# master_wiring.net
KiCad netlist of a schematic drawn in EAGLE
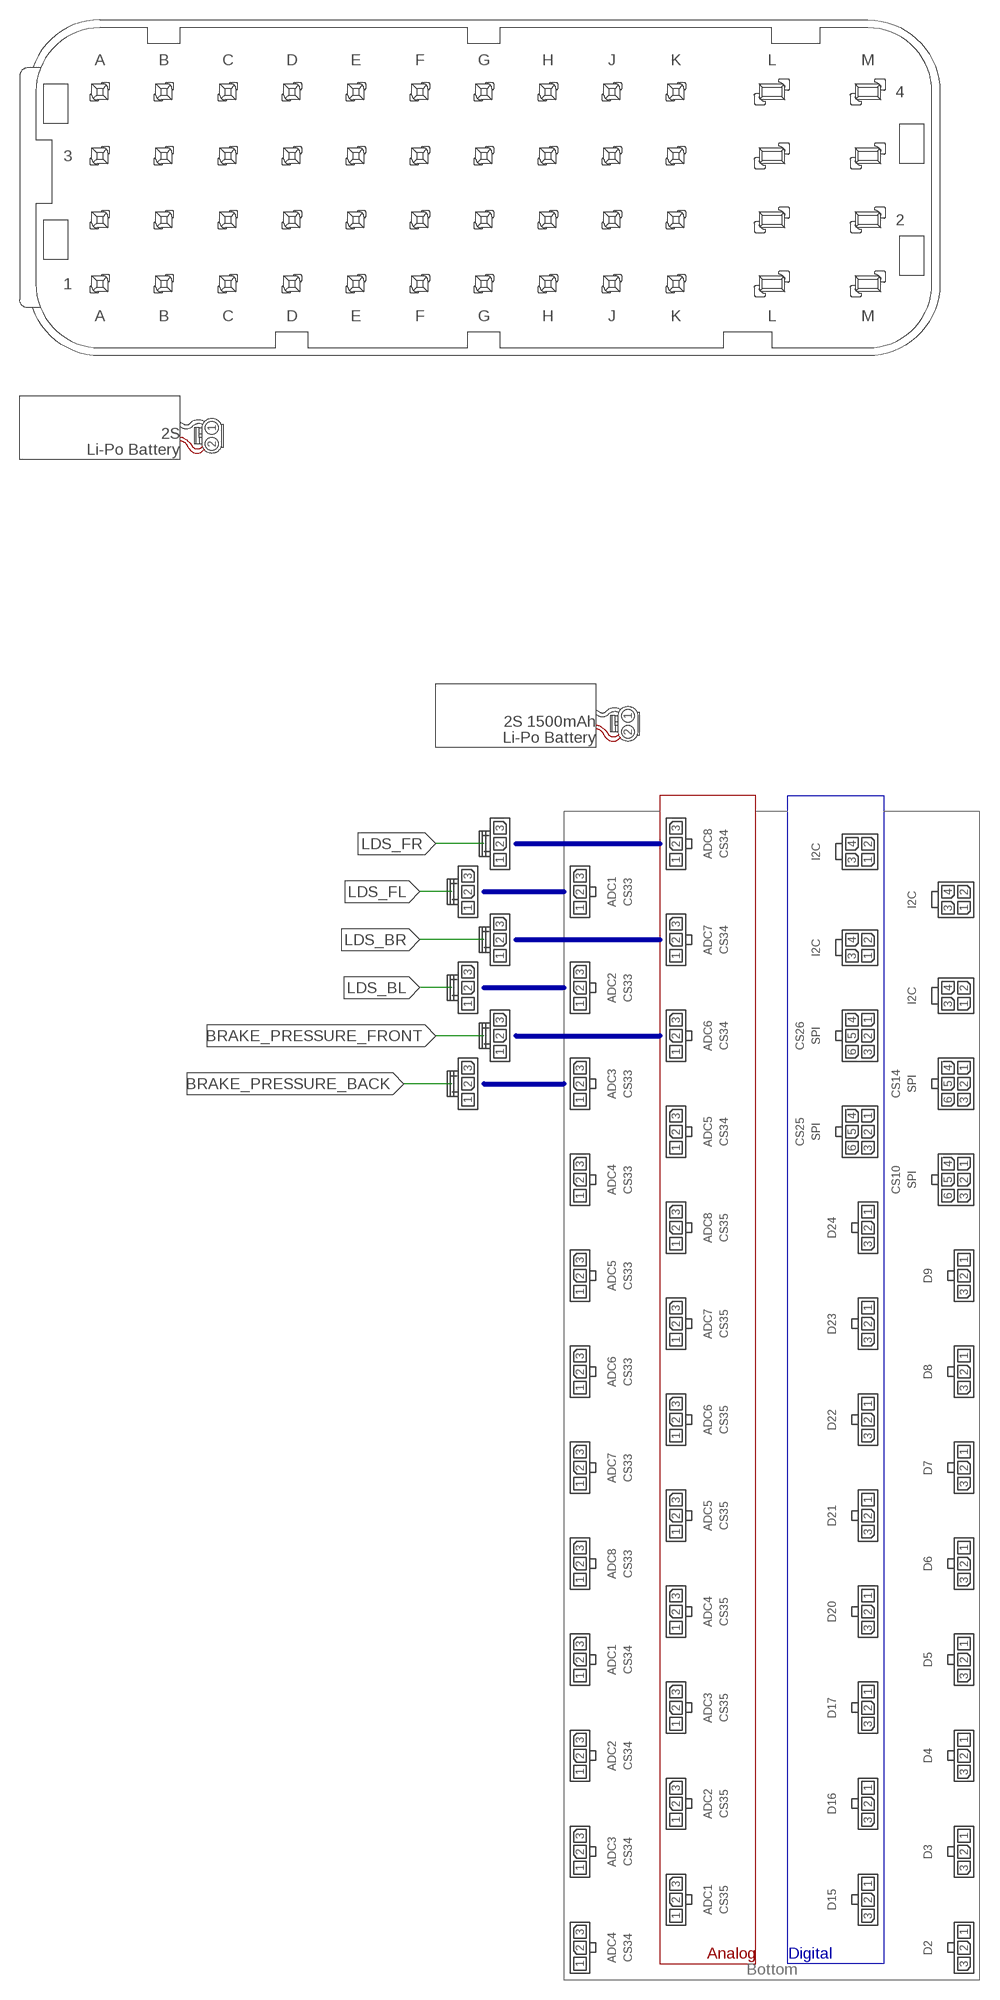
[diagram p0: schematic, sheet 1, part 1 of 2]
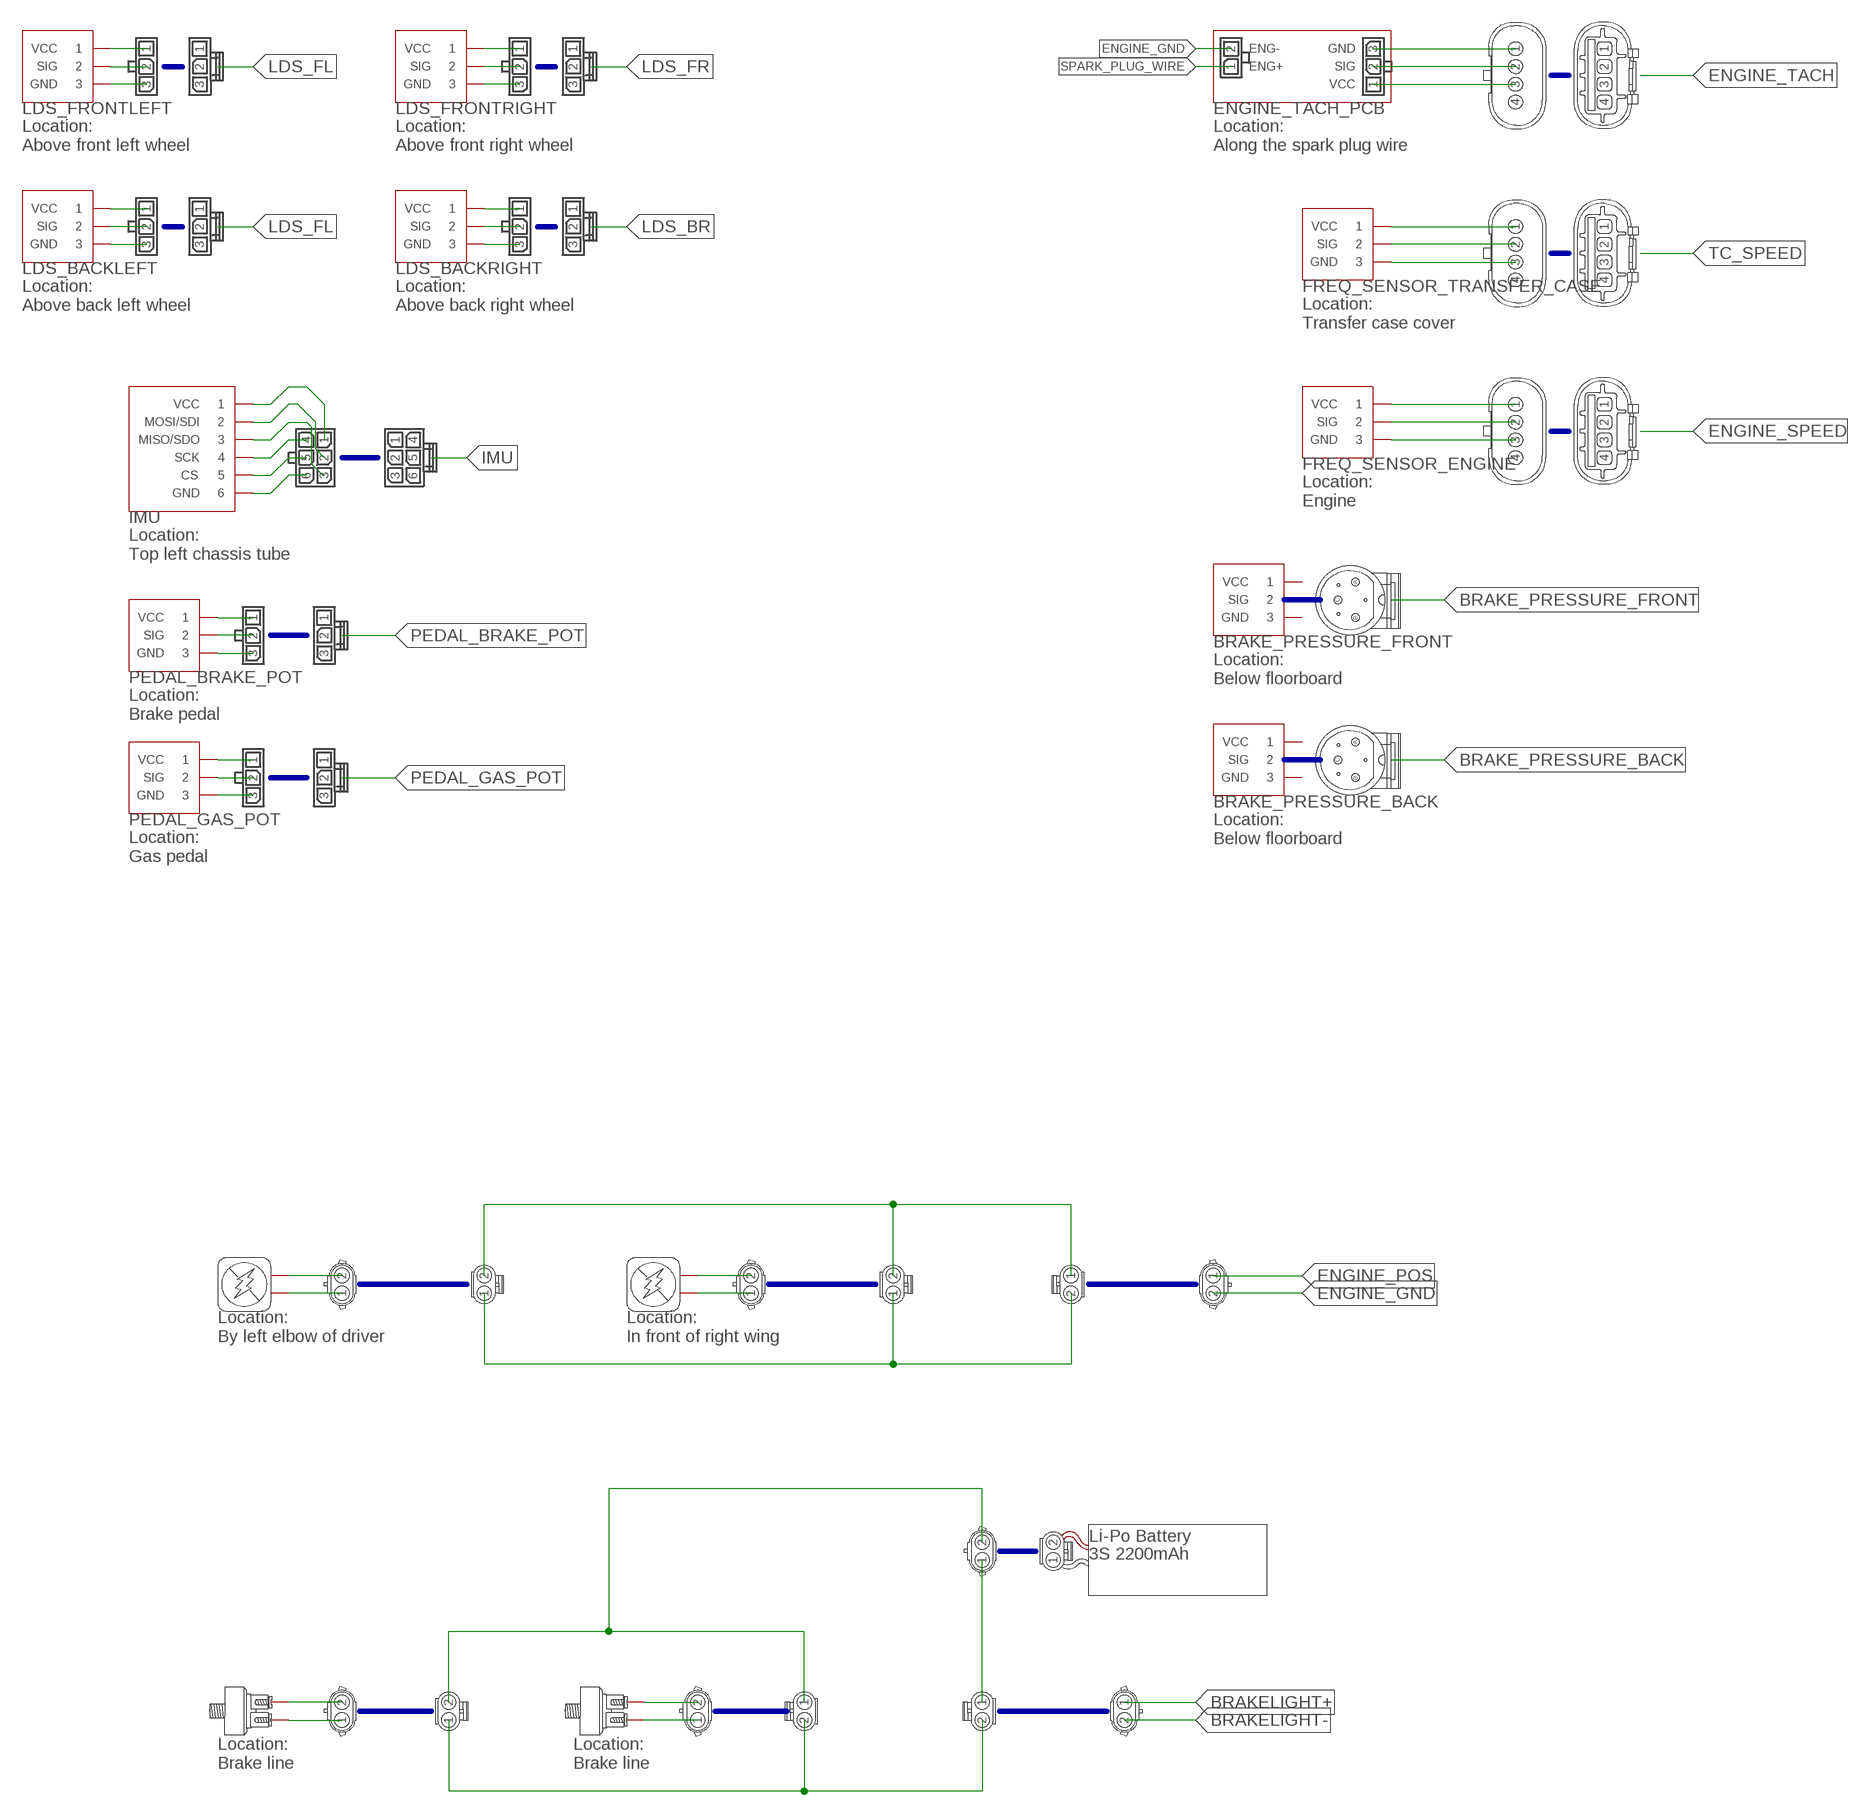
[diagram p1: schematic, sheet 1, part 2 of 2]

(export (version "E")
  (design (tool "Eeschema 10.0.6"))
  (components
    (comp (ref "BRAKE_PRESSURE_BACK")
      (value "SENSOR_1X3")
      (footprint "eagle-import:PINS_3")
      (libsource (lib "eagle-import") (part "SENSOR_1X3"))
    )
    (comp (ref "BRAKE_PRESSURE_FRONT")
      (value "SENSOR_1X3")
      (footprint "eagle-import:PINS_3")
      (libsource (lib "eagle-import") (part "SENSOR_1X3"))
    )
    (comp (ref "ENGINE_TACH_PCB")
      (value "ENGINE_TACH_PCB")
      (footprint "eagle-import:PINS_7")
      (libsource (lib "eagle-import") (part "ENGINE_TACH_PCB"))
    )
    (comp (ref "FREQ_SENSOR_ENGINE")
      (value "SENSOR_1X3")
      (footprint "eagle-import:PINS_3")
      (libsource (lib "eagle-import") (part "SENSOR_1X3"))
    )
    (comp (ref "FREQ_SENSOR_TRANSFER_CASE")
      (value "SENSOR_1X3")
      (footprint "eagle-import:PINS_3")
      (libsource (lib "eagle-import") (part "SENSOR_1X3"))
    )
    (comp (ref "IMU")
      (value "SENSOR_SPI_2X3")
      (footprint "eagle-import:PINS_7")
      (libsource (lib "eagle-import") (part "SENSOR_SPI_2X3"))
    )
    (comp (ref "LDS_BACKLEFT")
      (value "SENSOR_1X3")
      (footprint "eagle-import:PINS_3")
      (libsource (lib "eagle-import") (part "SENSOR_1X3"))
    )
    (comp (ref "LDS_BACKRIGHT")
      (value "SENSOR_1X3")
      (footprint "eagle-import:PINS_3")
      (libsource (lib "eagle-import") (part "SENSOR_1X3"))
    )
    (comp (ref "LDS_FRONTLEFT")
      (value "SENSOR_1X3")
      (footprint "eagle-import:PINS_3")
      (libsource (lib "eagle-import") (part "SENSOR_1X3"))
    )
    (comp (ref "LDS_FRONTRIGHT")
      (value "SENSOR_1X3")
      (footprint "eagle-import:PINS_3")
      (libsource (lib "eagle-import") (part "SENSOR_1X3"))
    )
    (comp (ref "PEDAL_BRAKE_POT")
      (value "SENSOR_1X3")
      (footprint "eagle-import:PINS_3")
      (libsource (lib "eagle-import") (part "SENSOR_1X3"))
    )
    (comp (ref "PEDAL_GAS_POT")
      (value "SENSOR_1X3")
      (footprint "eagle-import:PINS_3")
      (libsource (lib "eagle-import") (part "SENSOR_1X3"))
    )
    (comp (ref "U$1")
      (value "MICROFIT_1X3_MALE")
      (footprint "eagle-import:PINS_4")
      (libsource (lib "eagle-import") (part "MICROFIT_1X3_MALE"))
    )
    (comp (ref "U$2")
      (value "CMC_48PIN_PLUG_PCB")
      (footprint "eagle-import:PINS_49")
      (libsource (lib "eagle-import") (part "CMC_48PIN_PLUG_PCB"))
    )
    (comp (ref "U$3")
      (value "AUXDAQ_REV2")
      (footprint "eagle-import:PINS_200")
      (libsource (lib "eagle-import") (part "AUXDAQ_REV2"))
    )
    (comp (ref "U$4")
      (value "SKIDOO_KILLSWITCH")
      (footprint "eagle-import:PINS_3")
      (libsource (lib "eagle-import") (part "SKIDOO_KILLSWITCH"))
    )
    (comp (ref "U$5")
      (value "WEATHERPACK_1X2_MALE")
      (footprint "eagle-import:PINS_3")
      (libsource (lib "eagle-import") (part "WEATHERPACK_1X2_MALE"))
    )
    (comp (ref "U$6")
      (value "WEATHERPACK_1X2_FEMALE")
      (footprint "eagle-import:PINS_3")
      (libsource (lib "eagle-import") (part "WEATHERPACK_1X2_FEMALE"))
    )
    (comp (ref "U$7")
      (value "WEATHERPACK_1X2_MALE")
      (footprint "eagle-import:PINS_3")
      (libsource (lib "eagle-import") (part "WEATHERPACK_1X2_MALE"))
    )
    (comp (ref "U$8")
      (value "WEATHERPACK_1X2_MALE")
      (footprint "eagle-import:PINS_3")
      (libsource (lib "eagle-import") (part "WEATHERPACK_1X2_MALE"))
    )
    (comp (ref "U$9")
      (value "SKIDOO_KILLSWITCH")
      (footprint "eagle-import:PINS_3")
      (libsource (lib "eagle-import") (part "SKIDOO_KILLSWITCH"))
    )
    (comp (ref "U$10")
      (value "WEATHERPACK_1X2_FEMALE")
      (footprint "eagle-import:PINS_3")
      (libsource (lib "eagle-import") (part "WEATHERPACK_1X2_FEMALE"))
    )
    (comp (ref "U$11")
      (value "WEATHERPACK_1X2_FEMALE")
      (footprint "eagle-import:PINS_3")
      (libsource (lib "eagle-import") (part "WEATHERPACK_1X2_FEMALE"))
    )
    (comp (ref "U$12")
      (value "BRAKELIGHT_SWITCH_HYDRAULIC")
      (footprint "eagle-import:PINS_3")
      (libsource (lib "eagle-import") (part "BRAKELIGHT_SWITCH_HYDRAULIC"))
    )
    (comp (ref "U$13")
      (value "WEATHERPACK_1X2_MALE")
      (footprint "eagle-import:PINS_3")
      (libsource (lib "eagle-import") (part "WEATHERPACK_1X2_MALE"))
    )
    (comp (ref "U$14")
      (value "MICROFIT_1X3_MALE")
      (footprint "eagle-import:PINS_4")
      (libsource (lib "eagle-import") (part "MICROFIT_1X3_MALE"))
    )
    (comp (ref "U$15")
      (value "WEATHERPACK_1X2_FEMALE")
      (footprint "eagle-import:PINS_3")
      (libsource (lib "eagle-import") (part "WEATHERPACK_1X2_FEMALE"))
    )
    (comp (ref "U$16")
      (value "WEATHERPACK_1X2_MALE")
      (footprint "eagle-import:PINS_3")
      (libsource (lib "eagle-import") (part "WEATHERPACK_1X2_MALE"))
    )
    (comp (ref "U$17")
      (value "WEATHERPACK_1X2_MALE")
      (footprint "eagle-import:PINS_3")
      (libsource (lib "eagle-import") (part "WEATHERPACK_1X2_MALE"))
    )
    (comp (ref "U$18")
      (value "BRAKELIGHT_SWITCH_HYDRAULIC")
      (footprint "eagle-import:PINS_3")
      (libsource (lib "eagle-import") (part "BRAKELIGHT_SWITCH_HYDRAULIC"))
    )
    (comp (ref "U$19")
      (value "WEATHERPACK_1X2_FEMALE")
      (footprint "eagle-import:PINS_3")
      (libsource (lib "eagle-import") (part "WEATHERPACK_1X2_FEMALE"))
    )
    (comp (ref "U$20")
      (value "WEATHERPACK_1X2_FEMALE")
      (footprint "eagle-import:PINS_3")
      (libsource (lib "eagle-import") (part "WEATHERPACK_1X2_FEMALE"))
    )
    (comp (ref "U$21")
      (value "MICROFIT_1X3_MALE")
      (footprint "eagle-import:PINS_4")
      (libsource (lib "eagle-import") (part "MICROFIT_1X3_MALE"))
    )
    (comp (ref "U$22")
      (value "MICROFIT_1X3_MALE")
      (footprint "eagle-import:PINS_4")
      (libsource (lib "eagle-import") (part "MICROFIT_1X3_MALE"))
    )
    (comp (ref "U$23")
      (value "MICROFIT_2X3_MALE")
      (footprint "eagle-import:PINS_7")
      (libsource (lib "eagle-import") (part "MICROFIT_2X3_MALE"))
    )
    (comp (ref "U$24")
      (value "MICROFIT_1X3_MALE")
      (footprint "eagle-import:PINS_4")
      (libsource (lib "eagle-import") (part "MICROFIT_1X3_MALE"))
    )
    (comp (ref "U$25")
      (value "MICROFIT_1X3_MALE")
      (footprint "eagle-import:PINS_4")
      (libsource (lib "eagle-import") (part "MICROFIT_1X3_MALE"))
    )
    (comp (ref "U$26")
      (value "SQUBA_1X4_MALE")
      (footprint "eagle-import:PINS_5")
      (libsource (lib "eagle-import") (part "SQUBA_1X4_MALE"))
    )
    (comp (ref "U$27")
      (value "SQUBA_1X4_MALE")
      (footprint "eagle-import:PINS_5")
      (libsource (lib "eagle-import") (part "SQUBA_1X4_MALE"))
    )
    (comp (ref "U$28")
      (value "SQUBA_1X4_MALE")
      (footprint "eagle-import:PINS_5")
      (libsource (lib "eagle-import") (part "SQUBA_1X4_MALE"))
    )
    (comp (ref "U$29")
      (value "3S 2200mAh")
      (footprint "eagle-import:PINS_200")
      (libsource (lib "eagle-import") (part "LIPO_BATT"))
    )
    (comp (ref "U$30")
      (value "2S 1500mAh")
      (footprint "eagle-import:PINS_200")
      (libsource (lib "eagle-import") (part "LIPO_BATT"))
    )
    (comp (ref "U$31")
      (value "2S")
      (footprint "eagle-import:PINS_200")
      (libsource (lib "eagle-import") (part "LIPO_BATT"))
    )
    (comp (ref "U$32")
      (value "WEATHERPACK_1X2_MALE")
      (footprint "eagle-import:PINS_3")
      (libsource (lib "eagle-import") (part "WEATHERPACK_1X2_MALE"))
    )
    (comp (ref "U$33")
      (value "MICROFIT_2X3_FEMALE")
      (footprint "eagle-import:PINS_7")
      (libsource (lib "eagle-import") (part "MICROFIT_2X3_FEMALE"))
    )
    (comp (ref "U$34")
      (value "SQUBA_1X4_FEMALE")
      (footprint "eagle-import:PINS_5")
      (libsource (lib "eagle-import") (part "SQUBA_1X4_FEMALE"))
    )
    (comp (ref "U$35")
      (value "SQUBA_1X4_FEMALE")
      (footprint "eagle-import:PINS_5")
      (libsource (lib "eagle-import") (part "SQUBA_1X4_FEMALE"))
    )
    (comp (ref "U$36")
      (value "SQUBA_1X4_FEMALE")
      (footprint "eagle-import:PINS_5")
      (libsource (lib "eagle-import") (part "SQUBA_1X4_FEMALE"))
    )
    (comp (ref "U$37")
      (value "MICROFIT_1X3_FEMALE")
      (footprint "eagle-import:PINS_4")
      (libsource (lib "eagle-import") (part "MICROFIT_1X3_FEMALE"))
    )
    (comp (ref "U$38")
      (value "MICROFIT_1X3_FEMALE")
      (footprint "eagle-import:PINS_4")
      (libsource (lib "eagle-import") (part "MICROFIT_1X3_FEMALE"))
    )
    (comp (ref "U$39")
      (value "MICROFIT_1X3_FEMALE")
      (footprint "eagle-import:PINS_4")
      (libsource (lib "eagle-import") (part "MICROFIT_1X3_FEMALE"))
    )
    (comp (ref "U$40")
      (value "MICROFIT_1X3_FEMALE")
      (footprint "eagle-import:PINS_4")
      (libsource (lib "eagle-import") (part "MICROFIT_1X3_FEMALE"))
    )
    (comp (ref "U$41")
      (value "MICROFIT_1X3_FEMALE")
      (footprint "eagle-import:PINS_4")
      (libsource (lib "eagle-import") (part "MICROFIT_1X3_FEMALE"))
    )
    (comp (ref "U$42")
      (value "MICROFIT_1X3_FEMALE")
      (footprint "eagle-import:PINS_4")
      (libsource (lib "eagle-import") (part "MICROFIT_1X3_FEMALE"))
    )
    (comp (ref "U$43")
      (value "MICROFIT_1X3_FEMALE")
      (footprint "eagle-import:PINS_4")
      (libsource (lib "eagle-import") (part "MICROFIT_1X3_FEMALE"))
    )
    (comp (ref "U$44")
      (value "MICROFIT_1X3_FEMALE")
      (footprint "eagle-import:PINS_4")
      (libsource (lib "eagle-import") (part "MICROFIT_1X3_FEMALE"))
    )
    (comp (ref "U$45")
      (value "MICROFIT_1X3_FEMALE")
      (footprint "eagle-import:PINS_4")
      (libsource (lib "eagle-import") (part "MICROFIT_1X3_FEMALE"))
    )
    (comp (ref "U$46")
      (value "MICROFIT_1X3_FEMALE")
      (footprint "eagle-import:PINS_4")
      (libsource (lib "eagle-import") (part "MICROFIT_1X3_FEMALE"))
    )
    (comp (ref "U$47")
      (value "METRIPACK_3PIN_FEMALE")
      (footprint "eagle-import:PINS_3")
      (libsource (lib "eagle-import") (part "METRIPACK_3PIN_FEMALE"))
    )
    (comp (ref "U$48")
      (value "METRIPACK_3PIN_FEMALE")
      (footprint "eagle-import:PINS_3")
      (libsource (lib "eagle-import") (part "METRIPACK_3PIN_FEMALE"))
    )
    (comp (ref "U$49")
      (value "MICROFIT_1X3_FEMALE")
      (footprint "eagle-import:PINS_4")
      (libsource (lib "eagle-import") (part "MICROFIT_1X3_FEMALE"))
    )
    (comp (ref "U$50")
      (value "MICROFIT_1X3_FEMALE")
      (footprint "eagle-import:PINS_4")
      (libsource (lib "eagle-import") (part "MICROFIT_1X3_FEMALE"))
    )
  )
  (nets
    (net (code "2") (name "/B$1") (class "Default")
      (node (ref "IMU") (pin "P$1") (pinfunction "1_P$1") (pintype "bidirectional"))
      (node (ref "IMU") (pin "P$2") (pinfunction "2_P$2") (pintype "bidirectional"))
      (node (ref "IMU") (pin "P$3") (pinfunction "3_P$3") (pintype "bidirectional"))
      (node (ref "IMU") (pin "P$4") (pinfunction "4_P$4") (pintype "bidirectional"))
      (node (ref "IMU") (pin "P$5") (pinfunction "5_P$5") (pintype "bidirectional"))
      (node (ref "IMU") (pin "P$6") (pinfunction "6_P$6") (pintype "bidirectional"))
      (node (ref "U$23") (pin "P$1") (pinfunction "1_P$1") (pintype "bidirectional"))
      (node (ref "U$23") (pin "P$2") (pinfunction "2_P$2") (pintype "bidirectional"))
      (node (ref "U$23") (pin "P$3") (pinfunction "3_P$3") (pintype "bidirectional"))
      (node (ref "U$23") (pin "P$4") (pinfunction "4_P$4") (pintype "bidirectional"))
      (node (ref "U$23") (pin "P$5") (pinfunction "5_P$5") (pintype "bidirectional"))
      (node (ref "U$23") (pin "P$6") (pinfunction "6_P$6") (pintype "bidirectional"))
    )
    (net (code "3") (name "/L1") (class "Default")
      (node (ref "U$2") (pin "P$41") (pinfunction "L1_P$41") (pintype "power_in"))
    )
    (net (code "4") (name "/L2") (class "Default")
      (node (ref "U$2") (pin "P$42") (pinfunction "L2_P$42") (pintype "power_in"))
    )
    (net (code "5") (name "/L3") (class "Default")
      (node (ref "U$2") (pin "P$43") (pinfunction "L3_P$43") (pintype "power_in"))
    )
    (net (code "6") (name "/L4") (class "Default")
      (node (ref "U$2") (pin "P$44") (pinfunction "L4_P$44") (pintype "power_in"))
    )
    (net (code "7") (name "/M1") (class "Default")
      (node (ref "U$2") (pin "P$45") (pinfunction "M1_P$45") (pintype "power_in"))
    )
    (net (code "8") (name "/M2") (class "Default")
      (node (ref "U$2") (pin "P$46") (pinfunction "M2_P$46") (pintype "power_in"))
    )
    (net (code "9") (name "/M3") (class "Default")
      (node (ref "U$2") (pin "P$47") (pinfunction "M3_P$47") (pintype "power_in"))
    )
    (net (code "10") (name "/M4") (class "Default")
      (node (ref "U$2") (pin "P$48") (pinfunction "M4_P$48") (pintype "power_in"))
    )
    (net (code "12") (name "BRAKELIGHT+") (class "Default")
      (node (ref "U$16") (pin "P$2") (pinfunction "2_P$2") (pintype "bidirectional"))
    )
    (net (code "13") (name "BRAKELIGHT-") (class "Default")
      (node (ref "U$16") (pin "P$1") (pinfunction "1_P$1") (pintype "bidirectional"))
    )
    (net (code "16") (name "ENGINE_GND") (class "Default")
      (node (ref "ENGINE_TACH_PCB") (pin "P$2") (pinfunction "2_P$2") (pintype "bidirectional"))
      (node (ref "U$7") (pin "P$1") (pinfunction "1_P$1") (pintype "bidirectional"))
    )
    (net (code "17") (name "ENGINE_POS") (class "Default")
      (node (ref "U$7") (pin "P$2") (pinfunction "2_P$2") (pintype "bidirectional"))
    )
    (net (code "25") (name "Net-(ENGINE_TACH_PCB-6)") (class "Default")
      (node (ref "ENGINE_TACH_PCB") (pin "P$3") (pinfunction "6_P$3") (pintype "bidirectional"))
      (node (ref "U$26") (pin "P$3") (pinfunction "3_P$3") (pintype "bidirectional"))
    )
    (net (code "26") (name "Net-(ENGINE_TACH_PCB-7)") (class "Default")
      (node (ref "ENGINE_TACH_PCB") (pin "P$4") (pinfunction "7_P$4") (pintype "bidirectional"))
      (node (ref "U$26") (pin "P$2") (pinfunction "2_P$2") (pintype "bidirectional"))
    )
    (net (code "27") (name "Net-(ENGINE_TACH_PCB-8)") (class "Default")
      (node (ref "ENGINE_TACH_PCB") (pin "P$5") (pinfunction "8_P$5") (pintype "bidirectional"))
      (node (ref "U$26") (pin "P$1") (pinfunction "1_P$1") (pintype "bidirectional"))
    )
    (net (code "28") (name "Net-(FREQ_SENSOR_ENGINE-1)") (class "Default")
      (node (ref "FREQ_SENSOR_ENGINE") (pin "P$1") (pinfunction "1_P$1") (pintype "bidirectional"))
      (node (ref "U$27") (pin "P$1") (pinfunction "1_P$1") (pintype "bidirectional"))
    )
    (net (code "29") (name "Net-(FREQ_SENSOR_ENGINE-2)") (class "Default")
      (node (ref "FREQ_SENSOR_ENGINE") (pin "P$2") (pinfunction "2_P$2") (pintype "bidirectional"))
      (node (ref "U$27") (pin "P$2") (pinfunction "2_P$2") (pintype "bidirectional"))
    )
    (net (code "30") (name "Net-(FREQ_SENSOR_ENGINE-3)") (class "Default")
      (node (ref "FREQ_SENSOR_ENGINE") (pin "P$3") (pinfunction "3_P$3") (pintype "bidirectional"))
      (node (ref "U$27") (pin "P$3") (pinfunction "3_P$3") (pintype "bidirectional"))
    )
    (net (code "31") (name "Net-(FREQ_SENSOR_TRANSFER_CASE-1)") (class "Default")
      (node (ref "FREQ_SENSOR_TRANSFER_CASE") (pin "P$1") (pinfunction "1_P$1") (pintype "bidirectional"))
      (node (ref "U$28") (pin "P$1") (pinfunction "1_P$1") (pintype "bidirectional"))
    )
    (net (code "32") (name "Net-(FREQ_SENSOR_TRANSFER_CASE-2)") (class "Default")
      (node (ref "FREQ_SENSOR_TRANSFER_CASE") (pin "P$2") (pinfunction "2_P$2") (pintype "bidirectional"))
      (node (ref "U$28") (pin "P$2") (pinfunction "2_P$2") (pintype "bidirectional"))
    )
    (net (code "33") (name "Net-(FREQ_SENSOR_TRANSFER_CASE-3)") (class "Default")
      (node (ref "FREQ_SENSOR_TRANSFER_CASE") (pin "P$3") (pinfunction "3_P$3") (pintype "bidirectional"))
      (node (ref "U$28") (pin "P$3") (pinfunction "3_P$3") (pintype "bidirectional"))
    )
    (net (code "34") (name "Net-(LDS_BACKLEFT-1)") (class "Default")
      (node (ref "LDS_BACKLEFT") (pin "P$1") (pinfunction "1_P$1") (pintype "bidirectional"))
      (node (ref "U$14") (pin "P$1") (pinfunction "1_P$1") (pintype "bidirectional"))
    )
    (net (code "35") (name "Net-(LDS_BACKLEFT-2)") (class "Default")
      (node (ref "LDS_BACKLEFT") (pin "P$2") (pinfunction "2_P$2") (pintype "bidirectional"))
      (node (ref "U$14") (pin "P$2") (pinfunction "2_P$2") (pintype "bidirectional"))
    )
    (net (code "36") (name "Net-(LDS_BACKLEFT-3)") (class "Default")
      (node (ref "LDS_BACKLEFT") (pin "P$3") (pinfunction "3_P$3") (pintype "bidirectional"))
      (node (ref "U$14") (pin "P$3") (pinfunction "3_P$3") (pintype "bidirectional"))
    )
    (net (code "37") (name "Net-(LDS_BACKRIGHT-1)") (class "Default")
      (node (ref "LDS_BACKRIGHT") (pin "P$1") (pinfunction "1_P$1") (pintype "bidirectional"))
      (node (ref "U$22") (pin "P$1") (pinfunction "1_P$1") (pintype "bidirectional"))
    )
    (net (code "38") (name "Net-(LDS_BACKRIGHT-2)") (class "Default")
      (node (ref "LDS_BACKRIGHT") (pin "P$2") (pinfunction "2_P$2") (pintype "bidirectional"))
      (node (ref "U$22") (pin "P$2") (pinfunction "2_P$2") (pintype "bidirectional"))
    )
    (net (code "39") (name "Net-(LDS_BACKRIGHT-3)") (class "Default")
      (node (ref "LDS_BACKRIGHT") (pin "P$3") (pinfunction "3_P$3") (pintype "bidirectional"))
      (node (ref "U$22") (pin "P$3") (pinfunction "3_P$3") (pintype "bidirectional"))
    )
    (net (code "40") (name "Net-(LDS_FRONTLEFT-1)") (class "Default")
      (node (ref "LDS_FRONTLEFT") (pin "P$1") (pinfunction "1_P$1") (pintype "bidirectional"))
      (node (ref "U$1") (pin "P$1") (pinfunction "1_P$1") (pintype "bidirectional"))
    )
    (net (code "41") (name "Net-(LDS_FRONTLEFT-2)") (class "Default")
      (node (ref "LDS_FRONTLEFT") (pin "P$2") (pinfunction "2_P$2") (pintype "bidirectional"))
      (node (ref "U$1") (pin "P$2") (pinfunction "2_P$2") (pintype "bidirectional"))
    )
    (net (code "42") (name "Net-(LDS_FRONTLEFT-3)") (class "Default")
      (node (ref "LDS_FRONTLEFT") (pin "P$3") (pinfunction "3_P$3") (pintype "bidirectional"))
      (node (ref "U$1") (pin "P$3") (pinfunction "3_P$3") (pintype "bidirectional"))
    )
    (net (code "43") (name "Net-(LDS_FRONTRIGHT-1)") (class "Default")
      (node (ref "LDS_FRONTRIGHT") (pin "P$1") (pinfunction "1_P$1") (pintype "bidirectional"))
      (node (ref "U$21") (pin "P$1") (pinfunction "1_P$1") (pintype "bidirectional"))
    )
    (net (code "44") (name "Net-(LDS_FRONTRIGHT-2)") (class "Default")
      (node (ref "LDS_FRONTRIGHT") (pin "P$2") (pinfunction "2_P$2") (pintype "bidirectional"))
      (node (ref "U$21") (pin "P$2") (pinfunction "2_P$2") (pintype "bidirectional"))
    )
    (net (code "45") (name "Net-(LDS_FRONTRIGHT-3)") (class "Default")
      (node (ref "LDS_FRONTRIGHT") (pin "P$3") (pinfunction "3_P$3") (pintype "bidirectional"))
      (node (ref "U$21") (pin "P$3") (pinfunction "3_P$3") (pintype "bidirectional"))
    )
    (net (code "46") (name "Net-(PEDAL_BRAKE_POT-1)") (class "Default")
      (node (ref "PEDAL_BRAKE_POT") (pin "P$1") (pinfunction "1_P$1") (pintype "bidirectional"))
      (node (ref "U$24") (pin "P$1") (pinfunction "1_P$1") (pintype "bidirectional"))
    )
    (net (code "47") (name "Net-(PEDAL_BRAKE_POT-2)") (class "Default")
      (node (ref "PEDAL_BRAKE_POT") (pin "P$2") (pinfunction "2_P$2") (pintype "bidirectional"))
      (node (ref "U$24") (pin "P$2") (pinfunction "2_P$2") (pintype "bidirectional"))
    )
    (net (code "48") (name "Net-(PEDAL_BRAKE_POT-3)") (class "Default")
      (node (ref "PEDAL_BRAKE_POT") (pin "P$3") (pinfunction "3_P$3") (pintype "bidirectional"))
      (node (ref "U$24") (pin "P$3") (pinfunction "3_P$3") (pintype "bidirectional"))
    )
    (net (code "49") (name "Net-(PEDAL_GAS_POT-1)") (class "Default")
      (node (ref "PEDAL_GAS_POT") (pin "P$1") (pinfunction "1_P$1") (pintype "bidirectional"))
      (node (ref "U$25") (pin "P$1") (pinfunction "1_P$1") (pintype "bidirectional"))
    )
    (net (code "50") (name "Net-(PEDAL_GAS_POT-2)") (class "Default")
      (node (ref "PEDAL_GAS_POT") (pin "P$2") (pinfunction "2_P$2") (pintype "bidirectional"))
      (node (ref "U$25") (pin "P$2") (pinfunction "2_P$2") (pintype "bidirectional"))
    )
    (net (code "51") (name "Net-(PEDAL_GAS_POT-3)") (class "Default")
      (node (ref "PEDAL_GAS_POT") (pin "P$3") (pinfunction "3_P$3") (pintype "bidirectional"))
      (node (ref "U$25") (pin "P$3") (pinfunction "3_P$3") (pintype "bidirectional"))
    )
    (net (code "52") (name "Net-(U$5-1)") (class "Default")
      (node (ref "U$4") (pin "P$2") (pinfunction "P$2_P$2") (pintype "bidirectional"))
      (node (ref "U$5") (pin "P$1") (pinfunction "1_P$1") (pintype "bidirectional"))
    )
    (net (code "53") (name "Net-(U$5-2)") (class "Default")
      (node (ref "U$4") (pin "P$1") (pinfunction "P$1_P$1") (pintype "bidirectional"))
      (node (ref "U$5") (pin "P$2") (pinfunction "2_P$2") (pintype "bidirectional"))
    )
    (net (code "54") (name "Net-(U$8-1)") (class "Default")
      (node (ref "U$8") (pin "P$1") (pinfunction "1_P$1") (pintype "bidirectional"))
      (node (ref "U$9") (pin "P$2") (pinfunction "P$2_P$2") (pintype "bidirectional"))
    )
    (net (code "55") (name "Net-(U$8-2)") (class "Default")
      (node (ref "U$8") (pin "P$2") (pinfunction "2_P$2") (pintype "bidirectional"))
      (node (ref "U$9") (pin "P$1") (pinfunction "P$1_P$1") (pintype "bidirectional"))
    )
    (net (code "56") (name "Net-(U$10-1)") (class "Default")
      (node (ref "U$10") (pin "P$1") (pinfunction "1_P$1") (pintype "bidirectional"))
      (node (ref "U$11") (pin "P$2") (pinfunction "2_P$2") (pintype "bidirectional"))
      (node (ref "U$6") (pin "P$1") (pinfunction "1_P$1") (pintype "bidirectional"))
    )
    (net (code "57") (name "Net-(U$10-2)") (class "Default")
      (node (ref "U$10") (pin "P$2") (pinfunction "2_P$2") (pintype "bidirectional"))
      (node (ref "U$11") (pin "P$1") (pinfunction "1_P$1") (pintype "bidirectional"))
      (node (ref "U$6") (pin "P$2") (pinfunction "2_P$2") (pintype "bidirectional"))
    )
    (net (code "58") (name "Net-(U$13-1)") (class "Default")
      (node (ref "U$13") (pin "P$1") (pinfunction "1_P$1") (pintype "bidirectional"))
      (node (ref "U$18") (pin "P$1") (pinfunction "P$1_P$1") (pintype "bidirectional"))
    )
    (net (code "59") (name "Net-(U$13-2)") (class "Default")
      (node (ref "U$13") (pin "P$2") (pinfunction "2_P$2") (pintype "bidirectional"))
      (node (ref "U$18") (pin "P$2") (pinfunction "P$2_P$2") (pintype "bidirectional"))
    )
    (net (code "60") (name "Net-(U$15-1)") (class "Default")
      (node (ref "U$15") (pin "P$1") (pinfunction "1_P$1") (pintype "bidirectional"))
      (node (ref "U$19") (pin "P$2") (pinfunction "2_P$2") (pintype "bidirectional"))
      (node (ref "U$32") (pin "P$1") (pinfunction "1_P$1") (pintype "bidirectional"))
    )
    (net (code "61") (name "Net-(U$15-2)") (class "Default")
      (node (ref "U$15") (pin "P$2") (pinfunction "2_P$2") (pintype "bidirectional"))
      (node (ref "U$19") (pin "P$1") (pinfunction "1_P$1") (pintype "bidirectional"))
      (node (ref "U$20") (pin "P$2") (pinfunction "2_P$2") (pintype "bidirectional"))
    )
    (net (code "62") (name "Net-(U$17-1)") (class "Default")
      (node (ref "U$12") (pin "P$1") (pinfunction "P$1_P$1") (pintype "bidirectional"))
      (node (ref "U$17") (pin "P$1") (pinfunction "1_P$1") (pintype "bidirectional"))
    )
    (net (code "63") (name "Net-(U$17-2)") (class "Default")
      (node (ref "U$12") (pin "P$2") (pinfunction "P$2_P$2") (pintype "bidirectional"))
      (node (ref "U$17") (pin "P$2") (pinfunction "2_P$2") (pintype "bidirectional"))
    )
    (net (code "64") (name "Net-(U$20-1)") (class "Default")
      (node (ref "U$20") (pin "P$1") (pinfunction "1_P$1") (pintype "bidirectional"))
      (node (ref "U$32") (pin "P$2") (pinfunction "2_P$2") (pintype "bidirectional"))
    )
    (net (code "67") (name "SPARK_PLUG_WIRE") (class "Default")
      (node (ref "ENGINE_TACH_PCB") (pin "P$1") (pinfunction "1_P$1") (pintype "bidirectional"))
    )
    (net (code "69") (name "unconnected-(BRAKE_PRESSURE_BACK-1-PadP$1)") (class "Default")
      (node (ref "BRAKE_PRESSURE_BACK") (pin "P$1") (pinfunction "1_P$1") (pintype "bidirectional"))
    )
    (net (code "70") (name "unconnected-(BRAKE_PRESSURE_BACK-2-PadP$2)") (class "Default")
      (node (ref "BRAKE_PRESSURE_BACK") (pin "P$2") (pinfunction "2_P$2") (pintype "bidirectional"))
    )
    (net (code "71") (name "unconnected-(BRAKE_PRESSURE_BACK-3-PadP$3)") (class "Default")
      (node (ref "BRAKE_PRESSURE_BACK") (pin "P$3") (pinfunction "3_P$3") (pintype "bidirectional"))
    )
    (net (code "72") (name "unconnected-(BRAKE_PRESSURE_FRONT-1-PadP$1)") (class "Default")
      (node (ref "BRAKE_PRESSURE_FRONT") (pin "P$1") (pinfunction "1_P$1") (pintype "bidirectional"))
    )
    (net (code "73") (name "unconnected-(BRAKE_PRESSURE_FRONT-2-PadP$2)") (class "Default")
      (node (ref "BRAKE_PRESSURE_FRONT") (pin "P$2") (pinfunction "2_P$2") (pintype "bidirectional"))
    )
    (net (code "74") (name "unconnected-(BRAKE_PRESSURE_FRONT-3-PadP$3)") (class "Default")
      (node (ref "BRAKE_PRESSURE_FRONT") (pin "P$3") (pinfunction "3_P$3") (pintype "bidirectional"))
    )
    (net (code "75") (name "unconnected-(U$2-A1-PadP$1)") (class "Default")
      (node (ref "U$2") (pin "P$1") (pinfunction "A1_P$1") (pintype "bidirectional"))
    )
    (net (code "76") (name "unconnected-(U$2-A2-PadP$2)") (class "Default")
      (node (ref "U$2") (pin "P$2") (pinfunction "A2_P$2") (pintype "bidirectional"))
    )
    (net (code "77") (name "unconnected-(U$2-A3-PadP$3)") (class "Default")
      (node (ref "U$2") (pin "P$3") (pinfunction "A3_P$3") (pintype "bidirectional"))
    )
    (net (code "78") (name "unconnected-(U$2-A4-PadP$4)") (class "Default")
      (node (ref "U$2") (pin "P$4") (pinfunction "A4_P$4") (pintype "bidirectional"))
    )
    (net (code "79") (name "unconnected-(U$2-B1-PadP$5)") (class "Default")
      (node (ref "U$2") (pin "P$5") (pinfunction "B1_P$5") (pintype "bidirectional"))
    )
    (net (code "80") (name "unconnected-(U$2-B2-PadP$6)") (class "Default")
      (node (ref "U$2") (pin "P$6") (pinfunction "B2_P$6") (pintype "bidirectional"))
    )
    (net (code "81") (name "unconnected-(U$2-B3-PadP$7)") (class "Default")
      (node (ref "U$2") (pin "P$7") (pinfunction "B3_P$7") (pintype "bidirectional"))
    )
    (net (code "82") (name "unconnected-(U$2-B4-PadP$8)") (class "Default")
      (node (ref "U$2") (pin "P$8") (pinfunction "B4_P$8") (pintype "bidirectional"))
    )
    (net (code "83") (name "unconnected-(U$2-C1-PadP$9)") (class "Default")
      (node (ref "U$2") (pin "P$9") (pinfunction "C1_P$9") (pintype "bidirectional"))
    )
    (net (code "84") (name "unconnected-(U$2-C2-PadP$10)") (class "Default")
      (node (ref "U$2") (pin "P$10") (pinfunction "C2_P$10") (pintype "bidirectional"))
    )
    (net (code "85") (name "unconnected-(U$2-C3-PadP$11)") (class "Default")
      (node (ref "U$2") (pin "P$11") (pinfunction "C3_P$11") (pintype "bidirectional"))
    )
    (net (code "86") (name "unconnected-(U$2-C4-PadP$12)") (class "Default")
      (node (ref "U$2") (pin "P$12") (pinfunction "C4_P$12") (pintype "bidirectional"))
    )
    (net (code "87") (name "unconnected-(U$2-D1-PadP$13)") (class "Default")
      (node (ref "U$2") (pin "P$13") (pinfunction "D1_P$13") (pintype "bidirectional"))
    )
    (net (code "88") (name "unconnected-(U$2-D2-PadP$14)") (class "Default")
      (node (ref "U$2") (pin "P$14") (pinfunction "D2_P$14") (pintype "bidirectional"))
    )
    (net (code "89") (name "unconnected-(U$2-D3-PadP$15)") (class "Default")
      (node (ref "U$2") (pin "P$15") (pinfunction "D3_P$15") (pintype "bidirectional"))
    )
    (net (code "90") (name "unconnected-(U$2-D4-PadP$16)") (class "Default")
      (node (ref "U$2") (pin "P$16") (pinfunction "D4_P$16") (pintype "bidirectional"))
    )
    (net (code "91") (name "unconnected-(U$2-E1-PadP$17)") (class "Default")
      (node (ref "U$2") (pin "P$17") (pinfunction "E1_P$17") (pintype "bidirectional"))
    )
    (net (code "92") (name "unconnected-(U$2-E2-PadP$18)") (class "Default")
      (node (ref "U$2") (pin "P$18") (pinfunction "E2_P$18") (pintype "bidirectional"))
    )
    (net (code "93") (name "unconnected-(U$2-E3-PadP$19)") (class "Default")
      (node (ref "U$2") (pin "P$19") (pinfunction "E3_P$19") (pintype "bidirectional"))
    )
    (net (code "94") (name "unconnected-(U$2-E4-PadP$20)") (class "Default")
      (node (ref "U$2") (pin "P$20") (pinfunction "E4_P$20") (pintype "bidirectional"))
    )
    (net (code "95") (name "unconnected-(U$2-F1-PadP$21)") (class "Default")
      (node (ref "U$2") (pin "P$21") (pinfunction "F1_P$21") (pintype "bidirectional"))
    )
    (net (code "96") (name "unconnected-(U$2-F2-PadP$22)") (class "Default")
      (node (ref "U$2") (pin "P$22") (pinfunction "F2_P$22") (pintype "bidirectional"))
    )
    (net (code "97") (name "unconnected-(U$2-F3-PadP$23)") (class "Default")
      (node (ref "U$2") (pin "P$23") (pinfunction "F3_P$23") (pintype "bidirectional"))
    )
    (net (code "98") (name "unconnected-(U$2-F4-PadP$24)") (class "Default")
      (node (ref "U$2") (pin "P$24") (pinfunction "F4_P$24") (pintype "bidirectional"))
    )
    (net (code "99") (name "unconnected-(U$2-G1-PadP$25)") (class "Default")
      (node (ref "U$2") (pin "P$25") (pinfunction "G1_P$25") (pintype "bidirectional"))
    )
    (net (code "100") (name "unconnected-(U$2-G2-PadP$26)") (class "Default")
      (node (ref "U$2") (pin "P$26") (pinfunction "G2_P$26") (pintype "bidirectional"))
    )
    (net (code "101") (name "unconnected-(U$2-G3-PadP$27)") (class "Default")
      (node (ref "U$2") (pin "P$27") (pinfunction "G3_P$27") (pintype "bidirectional"))
    )
    (net (code "102") (name "unconnected-(U$2-G4-PadP$28)") (class "Default")
      (node (ref "U$2") (pin "P$28") (pinfunction "G4_P$28") (pintype "bidirectional"))
    )
    (net (code "103") (name "unconnected-(U$2-H1-PadP$29)") (class "Default")
      (node (ref "U$2") (pin "P$29") (pinfunction "H1_P$29") (pintype "bidirectional"))
    )
    (net (code "104") (name "unconnected-(U$2-H2-PadP$30)") (class "Default")
      (node (ref "U$2") (pin "P$30") (pinfunction "H2_P$30") (pintype "bidirectional"))
    )
    (net (code "105") (name "unconnected-(U$2-H3-PadP$31)") (class "Default")
      (node (ref "U$2") (pin "P$31") (pinfunction "H3_P$31") (pintype "bidirectional"))
    )
    (net (code "106") (name "unconnected-(U$2-H4-PadP$32)") (class "Default")
      (node (ref "U$2") (pin "P$32") (pinfunction "H4_P$32") (pintype "bidirectional"))
    )
    (net (code "107") (name "unconnected-(U$2-J1-PadP$33)") (class "Default")
      (node (ref "U$2") (pin "P$33") (pinfunction "J1_P$33") (pintype "bidirectional"))
    )
    (net (code "108") (name "unconnected-(U$2-J2-PadP$34)") (class "Default")
      (node (ref "U$2") (pin "P$34") (pinfunction "J2_P$34") (pintype "bidirectional"))
    )
    (net (code "109") (name "unconnected-(U$2-J3-PadP$35)") (class "Default")
      (node (ref "U$2") (pin "P$35") (pinfunction "J3_P$35") (pintype "bidirectional"))
    )
    (net (code "110") (name "unconnected-(U$2-J4-PadP$36)") (class "Default")
      (node (ref "U$2") (pin "P$36") (pinfunction "J4_P$36") (pintype "bidirectional"))
    )
    (net (code "111") (name "unconnected-(U$2-K1-PadP$37)") (class "Default")
      (node (ref "U$2") (pin "P$37") (pinfunction "K1_P$37") (pintype "bidirectional"))
    )
    (net (code "112") (name "unconnected-(U$2-K2-PadP$38)") (class "Default")
      (node (ref "U$2") (pin "P$38") (pinfunction "K2_P$38") (pintype "bidirectional"))
    )
    (net (code "113") (name "unconnected-(U$2-K3-PadP$39)") (class "Default")
      (node (ref "U$2") (pin "P$39") (pinfunction "K3_P$39") (pintype "bidirectional"))
    )
    (net (code "114") (name "unconnected-(U$2-K4-PadP$40)") (class "Default")
      (node (ref "U$2") (pin "P$40") (pinfunction "K4_P$40") (pintype "bidirectional"))
    )
    (net (code "115") (name "unconnected-(U$3-PadP$1)") (class "Default")
      (node (ref "U$3") (pin "P$1") (pinfunction "P$1_P$1") (pintype "bidirectional"))
    )
    (net (code "116") (name "unconnected-(U$3-PadP$2)") (class "Default")
      (node (ref "U$3") (pin "P$2") (pinfunction "P$2_P$2") (pintype "bidirectional"))
    )
    (net (code "117") (name "unconnected-(U$3-PadP$3)") (class "Default")
      (node (ref "U$3") (pin "P$3") (pinfunction "P$3_P$3") (pintype "bidirectional"))
    )
    (net (code "118") (name "unconnected-(U$3-PadP$4)") (class "Default")
      (node (ref "U$3") (pin "P$4") (pinfunction "P$4_P$4") (pintype "bidirectional"))
    )
    (net (code "119") (name "unconnected-(U$3-PadP$5)") (class "Default")
      (node (ref "U$3") (pin "P$5") (pinfunction "P$5_P$5") (pintype "bidirectional"))
    )
    (net (code "120") (name "unconnected-(U$3-PadP$6)") (class "Default")
      (node (ref "U$3") (pin "P$6") (pinfunction "P$6_P$6") (pintype "bidirectional"))
    )
    (net (code "121") (name "unconnected-(U$3-PadP$7)") (class "Default")
      (node (ref "U$3") (pin "P$7") (pinfunction "P$7_P$7") (pintype "bidirectional"))
    )
    (net (code "122") (name "unconnected-(U$3-PadP$8)") (class "Default")
      (node (ref "U$3") (pin "P$8") (pinfunction "P$8_P$8") (pintype "bidirectional"))
    )
    (net (code "123") (name "unconnected-(U$3-PadP$9)") (class "Default")
      (node (ref "U$3") (pin "P$9") (pinfunction "P$9_P$9") (pintype "bidirectional"))
    )
    (net (code "124") (name "unconnected-(U$3-PadP$10)") (class "Default")
      (node (ref "U$3") (pin "P$10") (pinfunction "P$10_P$10") (pintype "bidirectional"))
    )
    (net (code "125") (name "unconnected-(U$3-PadP$11)") (class "Default")
      (node (ref "U$3") (pin "P$11") (pinfunction "P$11_P$11") (pintype "bidirectional"))
    )
    (net (code "126") (name "unconnected-(U$3-PadP$12)") (class "Default")
      (node (ref "U$3") (pin "P$12") (pinfunction "P$12_P$12") (pintype "bidirectional"))
    )
    (net (code "127") (name "unconnected-(U$3-PadP$13)") (class "Default")
      (node (ref "U$3") (pin "P$13") (pinfunction "P$13_P$13") (pintype "bidirectional"))
    )
    (net (code "128") (name "unconnected-(U$3-PadP$14)") (class "Default")
      (node (ref "U$3") (pin "P$14") (pinfunction "P$14_P$14") (pintype "bidirectional"))
    )
    (net (code "129") (name "unconnected-(U$3-PadP$15)") (class "Default")
      (node (ref "U$3") (pin "P$15") (pinfunction "P$15_P$15") (pintype "bidirectional"))
    )
    (net (code "130") (name "unconnected-(U$3-PadP$16)") (class "Default")
      (node (ref "U$3") (pin "P$16") (pinfunction "P$16_P$16") (pintype "bidirectional"))
    )
    (net (code "131") (name "unconnected-(U$3-PadP$17)") (class "Default")
      (node (ref "U$3") (pin "P$17") (pinfunction "P$17_P$17") (pintype "bidirectional"))
    )
    (net (code "132") (name "unconnected-(U$3-PadP$18)") (class "Default")
      (node (ref "U$3") (pin "P$18") (pinfunction "P$18_P$18") (pintype "bidirectional"))
    )
    (net (code "133") (name "unconnected-(U$3-PadP$19)") (class "Default")
      (node (ref "U$3") (pin "P$19") (pinfunction "P$19_P$19") (pintype "bidirectional"))
    )
    (net (code "134") (name "unconnected-(U$3-PadP$20)") (class "Default")
      (node (ref "U$3") (pin "P$20") (pinfunction "P$20_P$20") (pintype "bidirectional"))
    )
    (net (code "135") (name "unconnected-(U$3-PadP$21)") (class "Default")
      (node (ref "U$3") (pin "P$21") (pinfunction "P$21_P$21") (pintype "bidirectional"))
    )
    (net (code "136") (name "unconnected-(U$3-PadP$22)") (class "Default")
      (node (ref "U$3") (pin "P$22") (pinfunction "P$22_P$22") (pintype "bidirectional"))
    )
    (net (code "137") (name "unconnected-(U$3-PadP$23)") (class "Default")
      (node (ref "U$3") (pin "P$23") (pinfunction "P$23_P$23") (pintype "bidirectional"))
    )
    (net (code "138") (name "unconnected-(U$3-PadP$24)") (class "Default")
      (node (ref "U$3") (pin "P$24") (pinfunction "P$24_P$24") (pintype "bidirectional"))
    )
    (net (code "139") (name "unconnected-(U$3-PadP$25)") (class "Default")
      (node (ref "U$3") (pin "P$25") (pinfunction "P$25_P$25") (pintype "bidirectional"))
    )
    (net (code "140") (name "unconnected-(U$3-PadP$26)") (class "Default")
      (node (ref "U$3") (pin "P$26") (pinfunction "P$26_P$26") (pintype "bidirectional"))
    )
    (net (code "141") (name "unconnected-(U$3-PadP$27)") (class "Default")
      (node (ref "U$3") (pin "P$27") (pinfunction "P$27_P$27") (pintype "bidirectional"))
    )
    (net (code "142") (name "unconnected-(U$3-PadP$28)") (class "Default")
      (node (ref "U$3") (pin "P$28") (pinfunction "P$28_P$28") (pintype "bidirectional"))
    )
    (net (code "143") (name "unconnected-(U$3-PadP$29)") (class "Default")
      (node (ref "U$3") (pin "P$29") (pinfunction "P$29_P$29") (pintype "bidirectional"))
    )
    (net (code "144") (name "unconnected-(U$3-PadP$30)") (class "Default")
      (node (ref "U$3") (pin "P$30") (pinfunction "P$30_P$30") (pintype "bidirectional"))
    )
    (net (code "145") (name "unconnected-(U$3-PadP$31)") (class "Default")
      (node (ref "U$3") (pin "P$31") (pinfunction "P$31_P$31") (pintype "bidirectional"))
    )
    (net (code "146") (name "unconnected-(U$3-PadP$32)") (class "Default")
      (node (ref "U$3") (pin "P$32") (pinfunction "P$32_P$32") (pintype "bidirectional"))
    )
    (net (code "147") (name "unconnected-(U$3-PadP$33)") (class "Default")
      (node (ref "U$3") (pin "P$33") (pinfunction "P$33_P$33") (pintype "bidirectional"))
    )
    (net (code "148") (name "unconnected-(U$3-PadP$34)") (class "Default")
      (node (ref "U$3") (pin "P$34") (pinfunction "P$34_P$34") (pintype "bidirectional"))
    )
    (net (code "149") (name "unconnected-(U$3-PadP$35)") (class "Default")
      (node (ref "U$3") (pin "P$35") (pinfunction "P$35_P$35") (pintype "bidirectional"))
    )
    (net (code "150") (name "unconnected-(U$3-PadP$36)") (class "Default")
      (node (ref "U$3") (pin "P$36") (pinfunction "P$36_P$36") (pintype "bidirectional"))
    )
    (net (code "151") (name "unconnected-(U$3-PadP$37)") (class "Default")
      (node (ref "U$3") (pin "P$37") (pinfunction "P$37_P$37") (pintype "bidirectional"))
    )
    (net (code "152") (name "unconnected-(U$3-PadP$38)") (class "Default")
      (node (ref "U$3") (pin "P$38") (pinfunction "P$38_P$38") (pintype "bidirectional"))
    )
    (net (code "153") (name "unconnected-(U$3-PadP$39)") (class "Default")
      (node (ref "U$3") (pin "P$39") (pinfunction "P$39_P$39") (pintype "bidirectional"))
    )
    (net (code "154") (name "unconnected-(U$3-PadP$40)") (class "Default")
      (node (ref "U$3") (pin "P$40") (pinfunction "P$40_P$40") (pintype "bidirectional"))
    )
    (net (code "155") (name "unconnected-(U$3-PadP$41)") (class "Default")
      (node (ref "U$3") (pin "P$41") (pinfunction "P$41_P$41") (pintype "bidirectional"))
    )
    (net (code "156") (name "unconnected-(U$3-PadP$42)") (class "Default")
      (node (ref "U$3") (pin "P$42") (pinfunction "P$42_P$42") (pintype "bidirectional"))
    )
    (net (code "157") (name "unconnected-(U$3-PadP$43)") (class "Default")
      (node (ref "U$3") (pin "P$43") (pinfunction "P$43_P$43") (pintype "bidirectional"))
    )
    (net (code "158") (name "unconnected-(U$3-PadP$44)") (class "Default")
      (node (ref "U$3") (pin "P$44") (pinfunction "P$44_P$44") (pintype "bidirectional"))
    )
    (net (code "159") (name "unconnected-(U$3-PadP$45)") (class "Default")
      (node (ref "U$3") (pin "P$45") (pinfunction "P$45_P$45") (pintype "bidirectional"))
    )
    (net (code "160") (name "unconnected-(U$3-PadP$46)") (class "Default")
      (node (ref "U$3") (pin "P$46") (pinfunction "P$46_P$46") (pintype "bidirectional"))
    )
    (net (code "161") (name "unconnected-(U$3-PadP$47)") (class "Default")
      (node (ref "U$3") (pin "P$47") (pinfunction "P$47_P$47") (pintype "bidirectional"))
    )
    (net (code "162") (name "unconnected-(U$3-PadP$48)") (class "Default")
      (node (ref "U$3") (pin "P$48") (pinfunction "P$48_P$48") (pintype "bidirectional"))
    )
    (net (code "163") (name "unconnected-(U$3-PadP$49)") (class "Default")
      (node (ref "U$3") (pin "P$49") (pinfunction "P$49_P$49") (pintype "bidirectional"))
    )
    (net (code "164") (name "unconnected-(U$3-PadP$50)") (class "Default")
      (node (ref "U$3") (pin "P$50") (pinfunction "P$50_P$50") (pintype "bidirectional"))
    )
    (net (code "165") (name "unconnected-(U$3-PadP$51)") (class "Default")
      (node (ref "U$3") (pin "P$51") (pinfunction "P$51_P$51") (pintype "bidirectional"))
    )
    (net (code "166") (name "unconnected-(U$3-PadP$52)") (class "Default")
      (node (ref "U$3") (pin "P$52") (pinfunction "P$52_P$52") (pintype "bidirectional"))
    )
    (net (code "167") (name "unconnected-(U$3-PadP$53)") (class "Default")
      (node (ref "U$3") (pin "P$53") (pinfunction "P$53_P$53") (pintype "bidirectional"))
    )
    (net (code "168") (name "unconnected-(U$3-PadP$54)") (class "Default")
      (node (ref "U$3") (pin "P$54") (pinfunction "P$54_P$54") (pintype "bidirectional"))
    )
    (net (code "169") (name "unconnected-(U$3-PadP$55)") (class "Default")
      (node (ref "U$3") (pin "P$55") (pinfunction "P$55_P$55") (pintype "bidirectional"))
    )
    (net (code "170") (name "unconnected-(U$3-PadP$56)") (class "Default")
      (node (ref "U$3") (pin "P$56") (pinfunction "P$56_P$56") (pintype "bidirectional"))
    )
    (net (code "171") (name "unconnected-(U$3-PadP$57)") (class "Default")
      (node (ref "U$3") (pin "P$57") (pinfunction "P$57_P$57") (pintype "bidirectional"))
    )
    (net (code "172") (name "unconnected-(U$3-PadP$58)") (class "Default")
      (node (ref "U$3") (pin "P$58") (pinfunction "P$58_P$58") (pintype "bidirectional"))
    )
    (net (code "173") (name "unconnected-(U$3-PadP$59)") (class "Default")
      (node (ref "U$3") (pin "P$59") (pinfunction "P$59_P$59") (pintype "bidirectional"))
    )
    (net (code "174") (name "unconnected-(U$3-PadP$60)") (class "Default")
      (node (ref "U$3") (pin "P$60") (pinfunction "P$60_P$60") (pintype "bidirectional"))
    )
    (net (code "175") (name "unconnected-(U$3-PadP$61)") (class "Default")
      (node (ref "U$3") (pin "P$61") (pinfunction "P$61_P$61") (pintype "bidirectional"))
    )
    (net (code "176") (name "unconnected-(U$3-PadP$62)") (class "Default")
      (node (ref "U$3") (pin "P$62") (pinfunction "P$62_P$62") (pintype "bidirectional"))
    )
    (net (code "177") (name "unconnected-(U$3-PadP$63)") (class "Default")
      (node (ref "U$3") (pin "P$63") (pinfunction "P$63_P$63") (pintype "bidirectional"))
    )
    (net (code "178") (name "unconnected-(U$3-PadP$64)") (class "Default")
      (node (ref "U$3") (pin "P$64") (pinfunction "P$64_P$64") (pintype "bidirectional"))
    )
    (net (code "179") (name "unconnected-(U$3-PadP$65)") (class "Default")
      (node (ref "U$3") (pin "P$65") (pinfunction "P$65_P$65") (pintype "bidirectional"))
    )
    (net (code "180") (name "unconnected-(U$3-PadP$66)") (class "Default")
      (node (ref "U$3") (pin "P$66") (pinfunction "P$66_P$66") (pintype "bidirectional"))
    )
    (net (code "181") (name "unconnected-(U$3-PadP$67)") (class "Default")
      (node (ref "U$3") (pin "P$67") (pinfunction "P$67_P$67") (pintype "bidirectional"))
    )
    (net (code "182") (name "unconnected-(U$3-PadP$68)") (class "Default")
      (node (ref "U$3") (pin "P$68") (pinfunction "P$68_P$68") (pintype "bidirectional"))
    )
    (net (code "183") (name "unconnected-(U$3-PadP$69)") (class "Default")
      (node (ref "U$3") (pin "P$69") (pinfunction "P$69_P$69") (pintype "bidirectional"))
    )
    (net (code "184") (name "unconnected-(U$3-PadP$70)") (class "Default")
      (node (ref "U$3") (pin "P$70") (pinfunction "P$70_P$70") (pintype "bidirectional"))
    )
    (net (code "185") (name "unconnected-(U$3-PadP$71)") (class "Default")
      (node (ref "U$3") (pin "P$71") (pinfunction "P$71_P$71") (pintype "bidirectional"))
    )
    (net (code "186") (name "unconnected-(U$3-PadP$72)") (class "Default")
      (node (ref "U$3") (pin "P$72") (pinfunction "P$72_P$72") (pintype "bidirectional"))
    )
    (net (code "187") (name "unconnected-(U$3-PadP$73)") (class "Default")
      (node (ref "U$3") (pin "P$73") (pinfunction "P$73_P$73") (pintype "bidirectional"))
    )
    (net (code "188") (name "unconnected-(U$3-PadP$74)") (class "Default")
      (node (ref "U$3") (pin "P$74") (pinfunction "P$74_P$74") (pintype "bidirectional"))
    )
    (net (code "189") (name "unconnected-(U$3-PadP$75)") (class "Default")
      (node (ref "U$3") (pin "P$75") (pinfunction "P$75_P$75") (pintype "bidirectional"))
    )
    (net (code "190") (name "unconnected-(U$3-PadP$76)") (class "Default")
      (node (ref "U$3") (pin "P$76") (pinfunction "P$76_P$76") (pintype "bidirectional"))
    )
    (net (code "191") (name "unconnected-(U$3-PadP$77)") (class "Default")
      (node (ref "U$3") (pin "P$77") (pinfunction "P$77_P$77") (pintype "bidirectional"))
    )
    (net (code "192") (name "unconnected-(U$3-PadP$78)") (class "Default")
      (node (ref "U$3") (pin "P$78") (pinfunction "P$78_P$78") (pintype "bidirectional"))
    )
    (net (code "193") (name "unconnected-(U$3-PadP$79)") (class "Default")
      (node (ref "U$3") (pin "P$79") (pinfunction "P$79_P$79") (pintype "bidirectional"))
    )
    (net (code "194") (name "unconnected-(U$3-PadP$80)") (class "Default")
      (node (ref "U$3") (pin "P$80") (pinfunction "P$80_P$80") (pintype "bidirectional"))
    )
    (net (code "195") (name "unconnected-(U$3-PadP$81)") (class "Default")
      (node (ref "U$3") (pin "P$81") (pinfunction "P$81_P$81") (pintype "bidirectional"))
    )
    (net (code "196") (name "unconnected-(U$3-PadP$82)") (class "Default")
      (node (ref "U$3") (pin "P$82") (pinfunction "P$82_P$82") (pintype "bidirectional"))
    )
    (net (code "197") (name "unconnected-(U$3-PadP$83)") (class "Default")
      (node (ref "U$3") (pin "P$83") (pinfunction "P$83_P$83") (pintype "bidirectional"))
    )
    (net (code "198") (name "unconnected-(U$3-PadP$84)") (class "Default")
      (node (ref "U$3") (pin "P$84") (pinfunction "P$84_P$84") (pintype "bidirectional"))
    )
    (net (code "199") (name "unconnected-(U$3-PadP$85)") (class "Default")
      (node (ref "U$3") (pin "P$85") (pinfunction "P$85_P$85") (pintype "bidirectional"))
    )
    (net (code "200") (name "unconnected-(U$3-PadP$86)") (class "Default")
      (node (ref "U$3") (pin "P$86") (pinfunction "P$86_P$86") (pintype "bidirectional"))
    )
    (net (code "201") (name "unconnected-(U$3-PadP$87)") (class "Default")
      (node (ref "U$3") (pin "P$87") (pinfunction "P$87_P$87") (pintype "bidirectional"))
    )
    (net (code "202") (name "unconnected-(U$3-PadP$88)") (class "Default")
      (node (ref "U$3") (pin "P$88") (pinfunction "P$88_P$88") (pintype "bidirectional"))
    )
    (net (code "203") (name "unconnected-(U$3-PadP$89)") (class "Default")
      (node (ref "U$3") (pin "P$89") (pinfunction "P$89_P$89") (pintype "bidirectional"))
    )
    (net (code "204") (name "unconnected-(U$3-PadP$90)") (class "Default")
      (node (ref "U$3") (pin "P$90") (pinfunction "P$90_P$90") (pintype "bidirectional"))
    )
    (net (code "205") (name "unconnected-(U$3-PadP$91)") (class "Default")
      (node (ref "U$3") (pin "P$91") (pinfunction "P$91_P$91") (pintype "bidirectional"))
    )
    (net (code "206") (name "unconnected-(U$3-PadP$92)") (class "Default")
      (node (ref "U$3") (pin "P$92") (pinfunction "P$92_P$92") (pintype "bidirectional"))
    )
    (net (code "207") (name "unconnected-(U$3-PadP$93)") (class "Default")
      (node (ref "U$3") (pin "P$93") (pinfunction "P$93_P$93") (pintype "bidirectional"))
    )
    (net (code "208") (name "unconnected-(U$3-PadP$94)") (class "Default")
      (node (ref "U$3") (pin "P$94") (pinfunction "P$94_P$94") (pintype "bidirectional"))
    )
    (net (code "209") (name "unconnected-(U$3-PadP$95)") (class "Default")
      (node (ref "U$3") (pin "P$95") (pinfunction "P$95_P$95") (pintype "bidirectional"))
    )
    (net (code "210") (name "unconnected-(U$3-PadP$96)") (class "Default")
      (node (ref "U$3") (pin "P$96") (pinfunction "P$96_P$96") (pintype "bidirectional"))
    )
    (net (code "211") (name "unconnected-(U$3-PadP$97)") (class "Default")
      (node (ref "U$3") (pin "P$97") (pinfunction "P$97_P$97") (pintype "bidirectional"))
    )
    (net (code "212") (name "unconnected-(U$3-PadP$98)") (class "Default")
      (node (ref "U$3") (pin "P$98") (pinfunction "P$98_P$98") (pintype "bidirectional"))
    )
    (net (code "213") (name "unconnected-(U$3-PadP$99)") (class "Default")
      (node (ref "U$3") (pin "P$99") (pinfunction "P$99_P$99") (pintype "bidirectional"))
    )
    (net (code "214") (name "unconnected-(U$3-PadP$100)") (class "Default")
      (node (ref "U$3") (pin "P$100") (pinfunction "P$100_P$100") (pintype "bidirectional"))
    )
    (net (code "215") (name "unconnected-(U$3-PadP$101)") (class "Default")
      (node (ref "U$3") (pin "P$101") (pinfunction "P$101_P$101") (pintype "bidirectional"))
    )
    (net (code "216") (name "unconnected-(U$3-PadP$102)") (class "Default")
      (node (ref "U$3") (pin "P$102") (pinfunction "P$102_P$102") (pintype "bidirectional"))
    )
    (net (code "217") (name "unconnected-(U$3-PadP$103)") (class "Default")
      (node (ref "U$3") (pin "P$103") (pinfunction "P$103_P$103") (pintype "bidirectional"))
    )
    (net (code "218") (name "unconnected-(U$3-PadP$104)") (class "Default")
      (node (ref "U$3") (pin "P$104") (pinfunction "P$104_P$104") (pintype "bidirectional"))
    )
    (net (code "219") (name "unconnected-(U$3-PadP$105)") (class "Default")
      (node (ref "U$3") (pin "P$105") (pinfunction "P$105_P$105") (pintype "bidirectional"))
    )
    (net (code "220") (name "unconnected-(U$3-PadP$106)") (class "Default")
      (node (ref "U$3") (pin "P$106") (pinfunction "P$106_P$106") (pintype "bidirectional"))
    )
    (net (code "221") (name "unconnected-(U$3-PadP$107)") (class "Default")
      (node (ref "U$3") (pin "P$107") (pinfunction "P$107_P$107") (pintype "bidirectional"))
    )
    (net (code "222") (name "unconnected-(U$3-PadP$108)") (class "Default")
      (node (ref "U$3") (pin "P$108") (pinfunction "P$108_P$108") (pintype "bidirectional"))
    )
    (net (code "223") (name "unconnected-(U$3-PadP$109)") (class "Default")
      (node (ref "U$3") (pin "P$109") (pinfunction "P$109_P$109") (pintype "bidirectional"))
    )
    (net (code "224") (name "unconnected-(U$3-PadP$110)") (class "Default")
      (node (ref "U$3") (pin "P$110") (pinfunction "P$110_P$110") (pintype "bidirectional"))
    )
    (net (code "225") (name "unconnected-(U$3-PadP$111)") (class "Default")
      (node (ref "U$3") (pin "P$111") (pinfunction "P$111_P$111") (pintype "bidirectional"))
    )
    (net (code "226") (name "unconnected-(U$3-PadP$112)") (class "Default")
      (node (ref "U$3") (pin "P$112") (pinfunction "P$112_P$112") (pintype "bidirectional"))
    )
    (net (code "227") (name "unconnected-(U$3-PadP$113)") (class "Default")
      (node (ref "U$3") (pin "P$113") (pinfunction "P$113_P$113") (pintype "bidirectional"))
    )
    (net (code "228") (name "unconnected-(U$3-PadP$114)") (class "Default")
      (node (ref "U$3") (pin "P$114") (pinfunction "P$114_P$114") (pintype "bidirectional"))
    )
    (net (code "229") (name "unconnected-(U$3-PadP$115)") (class "Default")
      (node (ref "U$3") (pin "P$115") (pinfunction "P$115_P$115") (pintype "bidirectional"))
    )
    (net (code "230") (name "unconnected-(U$3-PadP$116)") (class "Default")
      (node (ref "U$3") (pin "P$116") (pinfunction "P$116_P$116") (pintype "bidirectional"))
    )
    (net (code "231") (name "unconnected-(U$3-PadP$117)") (class "Default")
      (node (ref "U$3") (pin "P$117") (pinfunction "P$117_P$117") (pintype "bidirectional"))
    )
    (net (code "232") (name "unconnected-(U$3-PadP$118)") (class "Default")
      (node (ref "U$3") (pin "P$118") (pinfunction "P$118_P$118") (pintype "bidirectional"))
    )
    (net (code "233") (name "unconnected-(U$3-PadP$119)") (class "Default")
      (node (ref "U$3") (pin "P$119") (pinfunction "P$119_P$119") (pintype "bidirectional"))
    )
    (net (code "234") (name "unconnected-(U$3-PadP$120)") (class "Default")
      (node (ref "U$3") (pin "P$120") (pinfunction "P$120_P$120") (pintype "bidirectional"))
    )
    (net (code "235") (name "unconnected-(U$3-PadP$121)") (class "Default")
      (node (ref "U$3") (pin "P$121") (pinfunction "P$121_P$121") (pintype "bidirectional"))
    )
    (net (code "236") (name "unconnected-(U$3-PadP$122)") (class "Default")
      (node (ref "U$3") (pin "P$122") (pinfunction "P$122_P$122") (pintype "bidirectional"))
    )
    (net (code "237") (name "unconnected-(U$3-PadP$123)") (class "Default")
      (node (ref "U$3") (pin "P$123") (pinfunction "P$123_P$123") (pintype "bidirectional"))
    )
    (net (code "238") (name "unconnected-(U$3-PadP$124)") (class "Default")
      (node (ref "U$3") (pin "P$124") (pinfunction "P$124_P$124") (pintype "bidirectional"))
    )
    (net (code "239") (name "unconnected-(U$3-PadP$125)") (class "Default")
      (node (ref "U$3") (pin "P$125") (pinfunction "P$125_P$125") (pintype "bidirectional"))
    )
    (net (code "240") (name "unconnected-(U$3-PadP$126)") (class "Default")
      (node (ref "U$3") (pin "P$126") (pinfunction "P$126_P$126") (pintype "bidirectional"))
    )
    (net (code "241") (name "unconnected-(U$3-PadP$127)") (class "Default")
      (node (ref "U$3") (pin "P$127") (pinfunction "P$127_P$127") (pintype "bidirectional"))
    )
    (net (code "242") (name "unconnected-(U$3-PadP$128)") (class "Default")
      (node (ref "U$3") (pin "P$128") (pinfunction "P$128_P$128") (pintype "bidirectional"))
    )
    (net (code "243") (name "unconnected-(U$3-PadP$129)") (class "Default")
      (node (ref "U$3") (pin "P$129") (pinfunction "P$129_P$129") (pintype "bidirectional"))
    )
    (net (code "244") (name "unconnected-(U$3-PadP$130)") (class "Default")
      (node (ref "U$3") (pin "P$130") (pinfunction "P$130_P$130") (pintype "bidirectional"))
    )
    (net (code "245") (name "unconnected-(U$3-PadP$131)") (class "Default")
      (node (ref "U$3") (pin "P$131") (pinfunction "P$131_P$131") (pintype "bidirectional"))
    )
    (net (code "246") (name "unconnected-(U$3-PadP$132)") (class "Default")
      (node (ref "U$3") (pin "P$132") (pinfunction "P$132_P$132") (pintype "bidirectional"))
    )
    (net (code "247") (name "unconnected-(U$3-PadP$133)") (class "Default")
      (node (ref "U$3") (pin "P$133") (pinfunction "P$133_P$133") (pintype "bidirectional"))
    )
    (net (code "248") (name "unconnected-(U$3-PadP$134)") (class "Default")
      (node (ref "U$3") (pin "P$134") (pinfunction "P$134_P$134") (pintype "bidirectional"))
    )
    (net (code "249") (name "unconnected-(U$3-PadP$135)") (class "Default")
      (node (ref "U$3") (pin "P$135") (pinfunction "P$135_P$135") (pintype "bidirectional"))
    )
    (net (code "250") (name "unconnected-(U$3-PadP$136)") (class "Default")
      (node (ref "U$3") (pin "P$136") (pinfunction "P$136_P$136") (pintype "bidirectional"))
    )
    (net (code "251") (name "unconnected-(U$3-PadP$137)") (class "Default")
      (node (ref "U$3") (pin "P$137") (pinfunction "P$137_P$137") (pintype "bidirectional"))
    )
    (net (code "252") (name "unconnected-(U$3-PadP$138)") (class "Default")
      (node (ref "U$3") (pin "P$138") (pinfunction "P$138_P$138") (pintype "bidirectional"))
    )
    (net (code "253") (name "unconnected-(U$3-PadP$139)") (class "Default")
      (node (ref "U$3") (pin "P$139") (pinfunction "P$139_P$139") (pintype "bidirectional"))
    )
    (net (code "254") (name "unconnected-(U$3-PadP$140)") (class "Default")
      (node (ref "U$3") (pin "P$140") (pinfunction "P$140_P$140") (pintype "bidirectional"))
    )
    (net (code "255") (name "unconnected-(U$3-PadP$141)") (class "Default")
      (node (ref "U$3") (pin "P$141") (pinfunction "P$141_P$141") (pintype "bidirectional"))
    )
    (net (code "256") (name "unconnected-(U$3-PadP$142)") (class "Default")
      (node (ref "U$3") (pin "P$142") (pinfunction "P$142_P$142") (pintype "bidirectional"))
    )
    (net (code "257") (name "unconnected-(U$3-PadP$143)") (class "Default")
      (node (ref "U$3") (pin "P$143") (pinfunction "P$143_P$143") (pintype "bidirectional"))
    )
    (net (code "258") (name "unconnected-(U$3-PadP$144)") (class "Default")
      (node (ref "U$3") (pin "P$144") (pinfunction "P$144_P$144") (pintype "bidirectional"))
    )
    (net (code "259") (name "unconnected-(U$3-PadP$145)") (class "Default")
      (node (ref "U$3") (pin "P$145") (pinfunction "P$145_P$145") (pintype "bidirectional"))
    )
    (net (code "260") (name "unconnected-(U$3-PadP$146)") (class "Default")
      (node (ref "U$3") (pin "P$146") (pinfunction "P$146_P$146") (pintype "bidirectional"))
    )
    (net (code "261") (name "unconnected-(U$3-PadP$147)") (class "Default")
      (node (ref "U$3") (pin "P$147") (pinfunction "P$147_P$147") (pintype "bidirectional"))
    )
    (net (code "262") (name "unconnected-(U$3-PadP$148)") (class "Default")
      (node (ref "U$3") (pin "P$148") (pinfunction "P$148_P$148") (pintype "bidirectional"))
    )
    (net (code "263") (name "unconnected-(U$3-PadP$149)") (class "Default")
      (node (ref "U$3") (pin "P$149") (pinfunction "P$149_P$149") (pintype "bidirectional"))
    )
    (net (code "264") (name "unconnected-(U$3-PadP$150)") (class "Default")
      (node (ref "U$3") (pin "P$150") (pinfunction "P$150_P$150") (pintype "bidirectional"))
    )
    (net (code "265") (name "unconnected-(U$3-PadP$151)") (class "Default")
      (node (ref "U$3") (pin "P$151") (pinfunction "P$151_P$151") (pintype "bidirectional"))
    )
    (net (code "266") (name "unconnected-(U$3-PadP$152)") (class "Default")
      (node (ref "U$3") (pin "P$152") (pinfunction "P$152_P$152") (pintype "bidirectional"))
    )
    (net (code "267") (name "unconnected-(U$3-PadP$153)") (class "Default")
      (node (ref "U$3") (pin "P$153") (pinfunction "P$153_P$153") (pintype "bidirectional"))
    )
    (net (code "268") (name "unconnected-(U$3-PadP$154)") (class "Default")
      (node (ref "U$3") (pin "P$154") (pinfunction "P$154_P$154") (pintype "bidirectional"))
    )
    (net (code "269") (name "unconnected-(U$3-PadP$155)") (class "Default")
      (node (ref "U$3") (pin "P$155") (pinfunction "P$155_P$155") (pintype "bidirectional"))
    )
    (net (code "270") (name "unconnected-(U$3-PadP$156)") (class "Default")
      (node (ref "U$3") (pin "P$156") (pinfunction "P$156_P$156") (pintype "bidirectional"))
    )
    (net (code "271") (name "unconnected-(U$3-PadP$157)") (class "Default")
      (node (ref "U$3") (pin "P$157") (pinfunction "P$157_P$157") (pintype "bidirectional"))
    )
    (net (code "272") (name "unconnected-(U$3-PadP$158)") (class "Default")
      (node (ref "U$3") (pin "P$158") (pinfunction "P$158_P$158") (pintype "bidirectional"))
    )
    (net (code "273") (name "unconnected-(U$3-PadP$159)") (class "Default")
      (node (ref "U$3") (pin "P$159") (pinfunction "P$159_P$159") (pintype "bidirectional"))
    )
    (net (code "274") (name "unconnected-(U$3-PadP$160)") (class "Default")
      (node (ref "U$3") (pin "P$160") (pinfunction "P$160_P$160") (pintype "bidirectional"))
    )
    (net (code "275") (name "unconnected-(U$26-4-PadP$4)") (class "Default")
      (node (ref "U$26") (pin "P$4") (pinfunction "4_P$4") (pintype "bidirectional"))
    )
    (net (code "276") (name "unconnected-(U$27-4-PadP$4)") (class "Default")
      (node (ref "U$27") (pin "P$4") (pinfunction "4_P$4") (pintype "bidirectional"))
    )
    (net (code "277") (name "unconnected-(U$28-4-PadP$4)") (class "Default")
      (node (ref "U$28") (pin "P$4") (pinfunction "4_P$4") (pintype "bidirectional"))
    )
    (net (code "278") (name "unconnected-(U$29-1-PadP$1)") (class "Default")
      (node (ref "U$29") (pin "P$1") (pinfunction "1_P$1") (pintype "bidirectional"))
    )
    (net (code "279") (name "unconnected-(U$29-2-PadP$2)") (class "Default")
      (node (ref "U$29") (pin "P$2") (pinfunction "2_P$2") (pintype "bidirectional"))
    )
    (net (code "280") (name "unconnected-(U$30-1-PadP$1)") (class "Default")
      (node (ref "U$30") (pin "P$1") (pinfunction "1_P$1") (pintype "bidirectional"))
    )
    (net (code "281") (name "unconnected-(U$30-2-PadP$2)") (class "Default")
      (node (ref "U$30") (pin "P$2") (pinfunction "2_P$2") (pintype "bidirectional"))
    )
    (net (code "282") (name "unconnected-(U$31-1-PadP$1)") (class "Default")
      (node (ref "U$31") (pin "P$1") (pinfunction "1_P$1") (pintype "bidirectional"))
    )
    (net (code "283") (name "unconnected-(U$31-2-PadP$2)") (class "Default")
      (node (ref "U$31") (pin "P$2") (pinfunction "2_P$2") (pintype "bidirectional"))
    )
    (net (code "284") (name "unconnected-(U$33-1-PadP$1)") (class "Default")
      (node (ref "U$33") (pin "P$1") (pinfunction "1_P$1") (pintype "bidirectional"))
    )
    (net (code "285") (name "unconnected-(U$33-2-PadP$2)") (class "Default")
      (node (ref "U$33") (pin "P$2") (pinfunction "2_P$2") (pintype "bidirectional"))
    )
    (net (code "286") (name "unconnected-(U$33-3-PadP$3)") (class "Default")
      (node (ref "U$33") (pin "P$3") (pinfunction "3_P$3") (pintype "bidirectional"))
    )
    (net (code "287") (name "unconnected-(U$33-4-PadP$4)") (class "Default")
      (node (ref "U$33") (pin "P$4") (pinfunction "4_P$4") (pintype "bidirectional"))
    )
    (net (code "288") (name "unconnected-(U$33-5-PadP$5)") (class "Default")
      (node (ref "U$33") (pin "P$5") (pinfunction "5_P$5") (pintype "bidirectional"))
    )
    (net (code "289") (name "unconnected-(U$33-6-PadP$6)") (class "Default")
      (node (ref "U$33") (pin "P$6") (pinfunction "6_P$6") (pintype "bidirectional"))
    )
    (net (code "290") (name "unconnected-(U$34-1-PadP$4)") (class "Default")
      (node (ref "U$34") (pin "P$4") (pinfunction "1_P$4") (pintype "bidirectional"))
    )
    (net (code "291") (name "unconnected-(U$34-2-PadP$3)") (class "Default")
      (node (ref "U$34") (pin "P$3") (pinfunction "2_P$3") (pintype "bidirectional"))
    )
    (net (code "292") (name "unconnected-(U$34-3-PadP$2)") (class "Default")
      (node (ref "U$34") (pin "P$2") (pinfunction "3_P$2") (pintype "bidirectional"))
    )
    (net (code "293") (name "unconnected-(U$34-4-PadP$1)") (class "Default")
      (node (ref "U$34") (pin "P$1") (pinfunction "4_P$1") (pintype "bidirectional"))
    )
    (net (code "294") (name "unconnected-(U$35-1-PadP$4)") (class "Default")
      (node (ref "U$35") (pin "P$4") (pinfunction "1_P$4") (pintype "bidirectional"))
    )
    (net (code "295") (name "unconnected-(U$35-2-PadP$3)") (class "Default")
      (node (ref "U$35") (pin "P$3") (pinfunction "2_P$3") (pintype "bidirectional"))
    )
    (net (code "296") (name "unconnected-(U$35-3-PadP$2)") (class "Default")
      (node (ref "U$35") (pin "P$2") (pinfunction "3_P$2") (pintype "bidirectional"))
    )
    (net (code "297") (name "unconnected-(U$35-4-PadP$1)") (class "Default")
      (node (ref "U$35") (pin "P$1") (pinfunction "4_P$1") (pintype "bidirectional"))
    )
    (net (code "298") (name "unconnected-(U$36-1-PadP$4)") (class "Default")
      (node (ref "U$36") (pin "P$4") (pinfunction "1_P$4") (pintype "bidirectional"))
    )
    (net (code "299") (name "unconnected-(U$36-2-PadP$3)") (class "Default")
      (node (ref "U$36") (pin "P$3") (pinfunction "2_P$3") (pintype "bidirectional"))
    )
    (net (code "300") (name "unconnected-(U$36-3-PadP$2)") (class "Default")
      (node (ref "U$36") (pin "P$2") (pinfunction "3_P$2") (pintype "bidirectional"))
    )
    (net (code "301") (name "unconnected-(U$36-4-PadP$1)") (class "Default")
      (node (ref "U$36") (pin "P$1") (pinfunction "4_P$1") (pintype "bidirectional"))
    )
    (net (code "302") (name "unconnected-(U$37-1-PadP$1)") (class "Default")
      (node (ref "U$37") (pin "P$1") (pinfunction "1_P$1") (pintype "bidirectional"))
    )
    (net (code "303") (name "unconnected-(U$37-2-PadP$2)") (class "Default")
      (node (ref "U$37") (pin "P$2") (pinfunction "2_P$2") (pintype "bidirectional"))
    )
    (net (code "304") (name "unconnected-(U$37-3-PadP$3)") (class "Default")
      (node (ref "U$37") (pin "P$3") (pinfunction "3_P$3") (pintype "bidirectional"))
    )
    (net (code "305") (name "unconnected-(U$38-1-PadP$1)") (class "Default")
      (node (ref "U$38") (pin "P$1") (pinfunction "1_P$1") (pintype "bidirectional"))
    )
    (net (code "306") (name "unconnected-(U$38-2-PadP$2)") (class "Default")
      (node (ref "U$38") (pin "P$2") (pinfunction "2_P$2") (pintype "bidirectional"))
    )
    (net (code "307") (name "unconnected-(U$38-3-PadP$3)") (class "Default")
      (node (ref "U$38") (pin "P$3") (pinfunction "3_P$3") (pintype "bidirectional"))
    )
    (net (code "308") (name "unconnected-(U$39-1-PadP$1)") (class "Default")
      (node (ref "U$39") (pin "P$1") (pinfunction "1_P$1") (pintype "bidirectional"))
    )
    (net (code "309") (name "unconnected-(U$39-2-PadP$2)") (class "Default")
      (node (ref "U$39") (pin "P$2") (pinfunction "2_P$2") (pintype "bidirectional"))
    )
    (net (code "310") (name "unconnected-(U$39-3-PadP$3)") (class "Default")
      (node (ref "U$39") (pin "P$3") (pinfunction "3_P$3") (pintype "bidirectional"))
    )
    (net (code "311") (name "unconnected-(U$40-1-PadP$1)") (class "Default")
      (node (ref "U$40") (pin "P$1") (pinfunction "1_P$1") (pintype "bidirectional"))
    )
    (net (code "312") (name "unconnected-(U$40-2-PadP$2)") (class "Default")
      (node (ref "U$40") (pin "P$2") (pinfunction "2_P$2") (pintype "bidirectional"))
    )
    (net (code "313") (name "unconnected-(U$40-3-PadP$3)") (class "Default")
      (node (ref "U$40") (pin "P$3") (pinfunction "3_P$3") (pintype "bidirectional"))
    )
    (net (code "314") (name "unconnected-(U$41-1-PadP$1)") (class "Default")
      (node (ref "U$41") (pin "P$1") (pinfunction "1_P$1") (pintype "bidirectional"))
    )
    (net (code "315") (name "unconnected-(U$41-2-PadP$2)") (class "Default")
      (node (ref "U$41") (pin "P$2") (pinfunction "2_P$2") (pintype "bidirectional"))
    )
    (net (code "316") (name "unconnected-(U$41-3-PadP$3)") (class "Default")
      (node (ref "U$41") (pin "P$3") (pinfunction "3_P$3") (pintype "bidirectional"))
    )
    (net (code "317") (name "unconnected-(U$42-1-PadP$1)") (class "Default")
      (node (ref "U$42") (pin "P$1") (pinfunction "1_P$1") (pintype "bidirectional"))
    )
    (net (code "318") (name "unconnected-(U$42-2-PadP$2)") (class "Default")
      (node (ref "U$42") (pin "P$2") (pinfunction "2_P$2") (pintype "bidirectional"))
    )
    (net (code "319") (name "unconnected-(U$42-3-PadP$3)") (class "Default")
      (node (ref "U$42") (pin "P$3") (pinfunction "3_P$3") (pintype "bidirectional"))
    )
    (net (code "320") (name "unconnected-(U$43-1-PadP$1)") (class "Default")
      (node (ref "U$43") (pin "P$1") (pinfunction "1_P$1") (pintype "bidirectional"))
    )
    (net (code "321") (name "unconnected-(U$43-2-PadP$2)") (class "Default")
      (node (ref "U$43") (pin "P$2") (pinfunction "2_P$2") (pintype "bidirectional"))
    )
    (net (code "322") (name "unconnected-(U$43-3-PadP$3)") (class "Default")
      (node (ref "U$43") (pin "P$3") (pinfunction "3_P$3") (pintype "bidirectional"))
    )
    (net (code "323") (name "unconnected-(U$44-1-PadP$1)") (class "Default")
      (node (ref "U$44") (pin "P$1") (pinfunction "1_P$1") (pintype "bidirectional"))
    )
    (net (code "324") (name "unconnected-(U$44-2-PadP$2)") (class "Default")
      (node (ref "U$44") (pin "P$2") (pinfunction "2_P$2") (pintype "bidirectional"))
    )
    (net (code "325") (name "unconnected-(U$44-3-PadP$3)") (class "Default")
      (node (ref "U$44") (pin "P$3") (pinfunction "3_P$3") (pintype "bidirectional"))
    )
    (net (code "326") (name "unconnected-(U$45-1-PadP$1)") (class "Default")
      (node (ref "U$45") (pin "P$1") (pinfunction "1_P$1") (pintype "bidirectional"))
    )
    (net (code "327") (name "unconnected-(U$45-2-PadP$2)") (class "Default")
      (node (ref "U$45") (pin "P$2") (pinfunction "2_P$2") (pintype "bidirectional"))
    )
    (net (code "328") (name "unconnected-(U$45-3-PadP$3)") (class "Default")
      (node (ref "U$45") (pin "P$3") (pinfunction "3_P$3") (pintype "bidirectional"))
    )
    (net (code "329") (name "unconnected-(U$46-1-PadP$1)") (class "Default")
      (node (ref "U$46") (pin "P$1") (pinfunction "1_P$1") (pintype "bidirectional"))
    )
    (net (code "330") (name "unconnected-(U$46-2-PadP$2)") (class "Default")
      (node (ref "U$46") (pin "P$2") (pinfunction "2_P$2") (pintype "bidirectional"))
    )
    (net (code "331") (name "unconnected-(U$46-3-PadP$3)") (class "Default")
      (node (ref "U$46") (pin "P$3") (pinfunction "3_P$3") (pintype "bidirectional"))
    )
    (net (code "332") (name "unconnected-(U$47-1-PadP$1)") (class "Default")
      (node (ref "U$47") (pin "P$1") (pinfunction "1_P$1") (pintype "bidirectional"))
    )
    (net (code "333") (name "unconnected-(U$47-2-PadP$2)") (class "Default")
      (node (ref "U$47") (pin "P$2") (pinfunction "2_P$2") (pintype "bidirectional"))
    )
    (net (code "334") (name "unconnected-(U$47-3-PadP$3)") (class "Default")
      (node (ref "U$47") (pin "P$3") (pinfunction "3_P$3") (pintype "bidirectional"))
    )
    (net (code "335") (name "unconnected-(U$48-1-PadP$1)") (class "Default")
      (node (ref "U$48") (pin "P$1") (pinfunction "1_P$1") (pintype "bidirectional"))
    )
    (net (code "336") (name "unconnected-(U$48-2-PadP$2)") (class "Default")
      (node (ref "U$48") (pin "P$2") (pinfunction "2_P$2") (pintype "bidirectional"))
    )
    (net (code "337") (name "unconnected-(U$48-3-PadP$3)") (class "Default")
      (node (ref "U$48") (pin "P$3") (pinfunction "3_P$3") (pintype "bidirectional"))
    )
    (net (code "338") (name "unconnected-(U$49-1-PadP$1)") (class "Default")
      (node (ref "U$49") (pin "P$1") (pinfunction "1_P$1") (pintype "bidirectional"))
    )
    (net (code "339") (name "unconnected-(U$49-2-PadP$2)") (class "Default")
      (node (ref "U$49") (pin "P$2") (pinfunction "2_P$2") (pintype "bidirectional"))
    )
    (net (code "340") (name "unconnected-(U$49-3-PadP$3)") (class "Default")
      (node (ref "U$49") (pin "P$3") (pinfunction "3_P$3") (pintype "bidirectional"))
    )
    (net (code "341") (name "unconnected-(U$50-1-PadP$1)") (class "Default")
      (node (ref "U$50") (pin "P$1") (pinfunction "1_P$1") (pintype "bidirectional"))
    )
    (net (code "342") (name "unconnected-(U$50-2-PadP$2)") (class "Default")
      (node (ref "U$50") (pin "P$2") (pinfunction "2_P$2") (pintype "bidirectional"))
    )
    (net (code "343") (name "unconnected-(U$50-3-PadP$3)") (class "Default")
      (node (ref "U$50") (pin "P$3") (pinfunction "3_P$3") (pintype "bidirectional"))
    )
  )
)
